# LS1C300B_176A_Msystem.net
KiCad netlist of a schematic drawn in Altium Designer
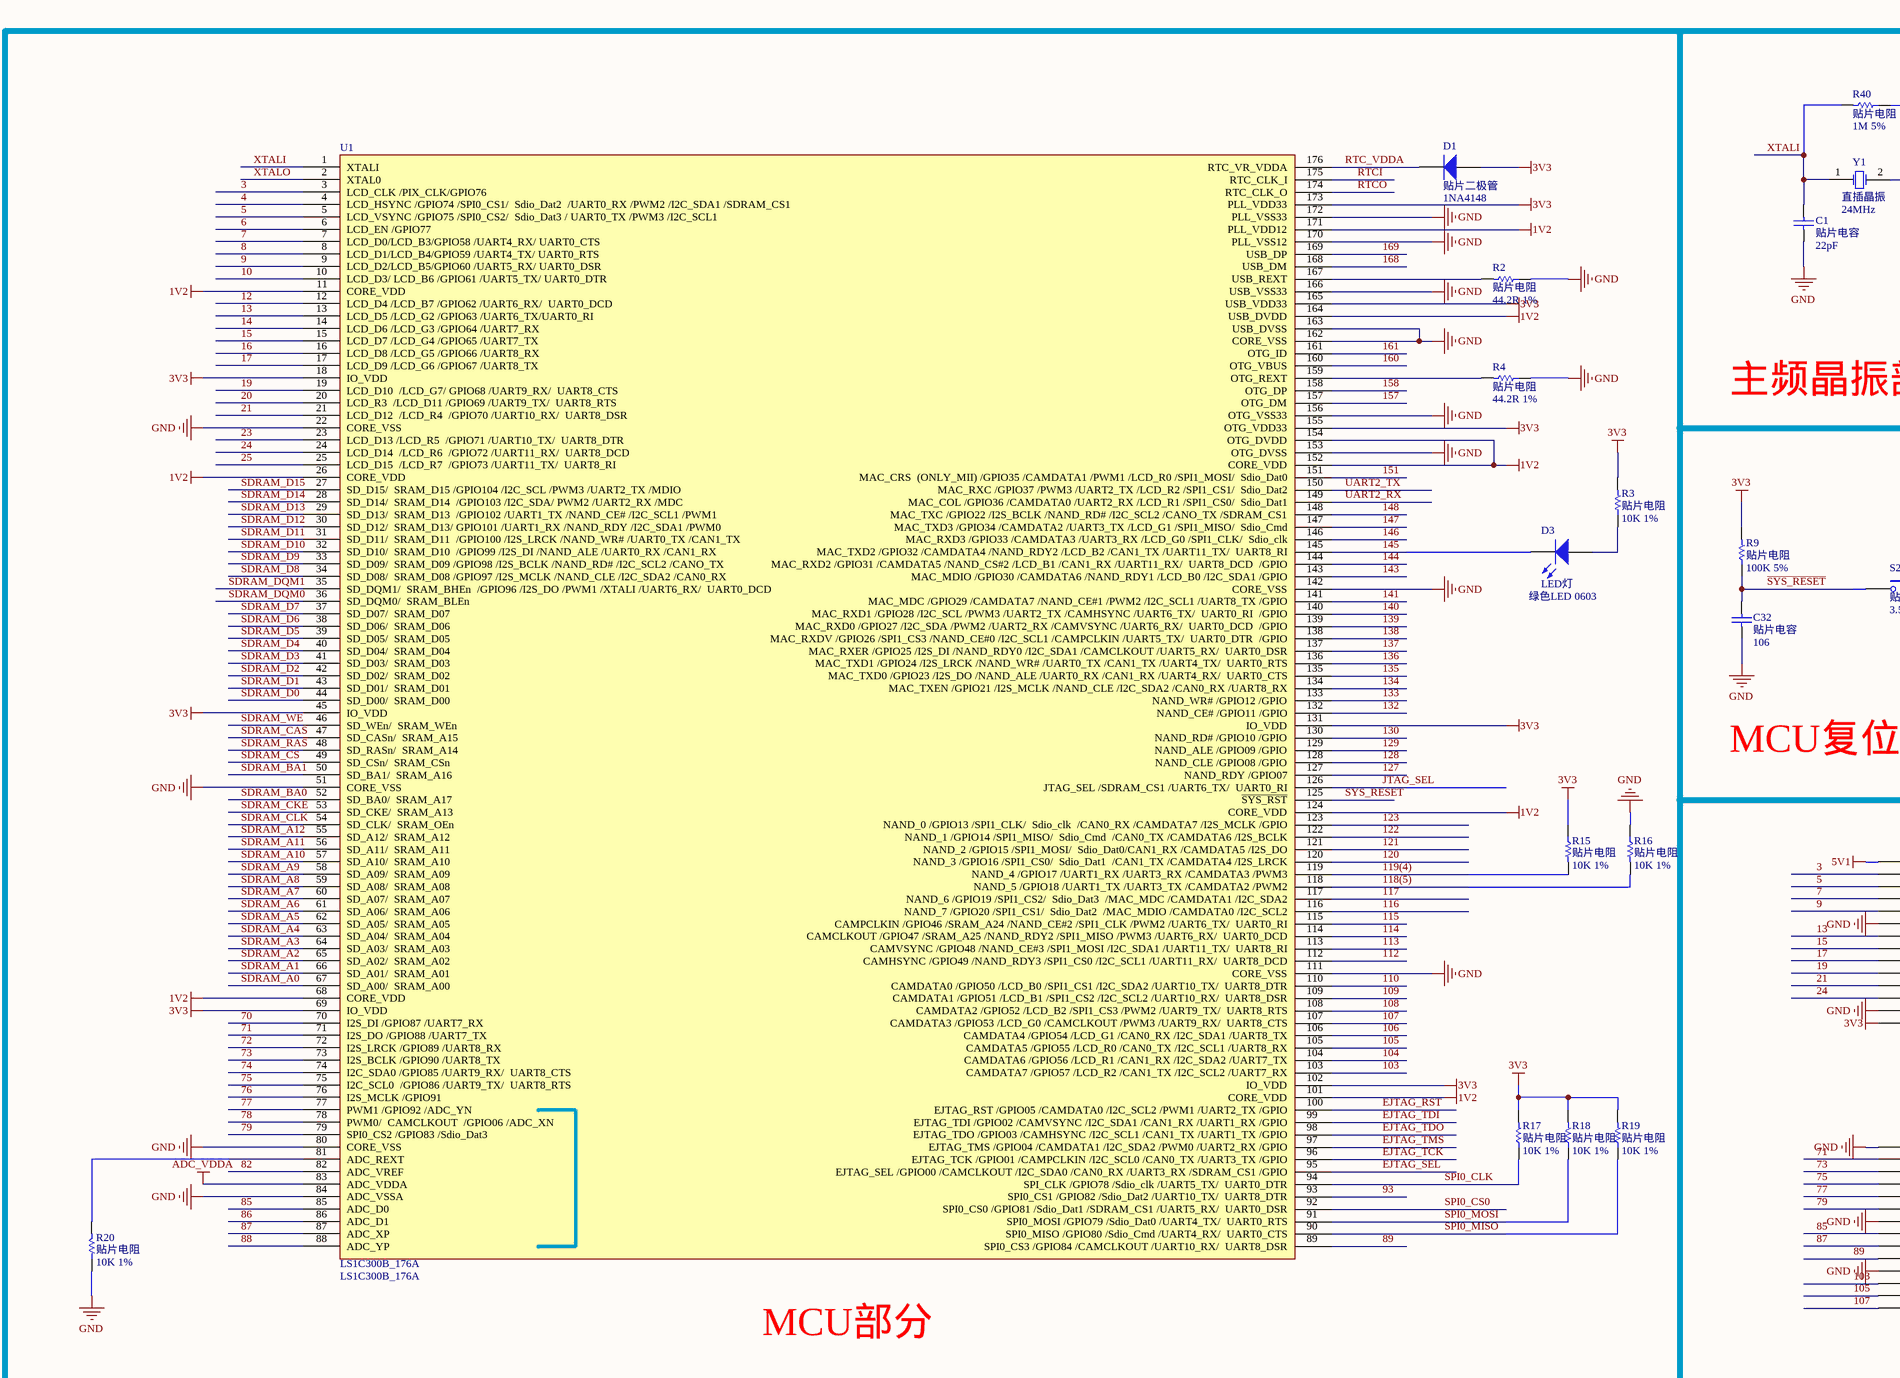
[diagram p0: LS1C300B_176A_Msystem.SchDoc, top left]
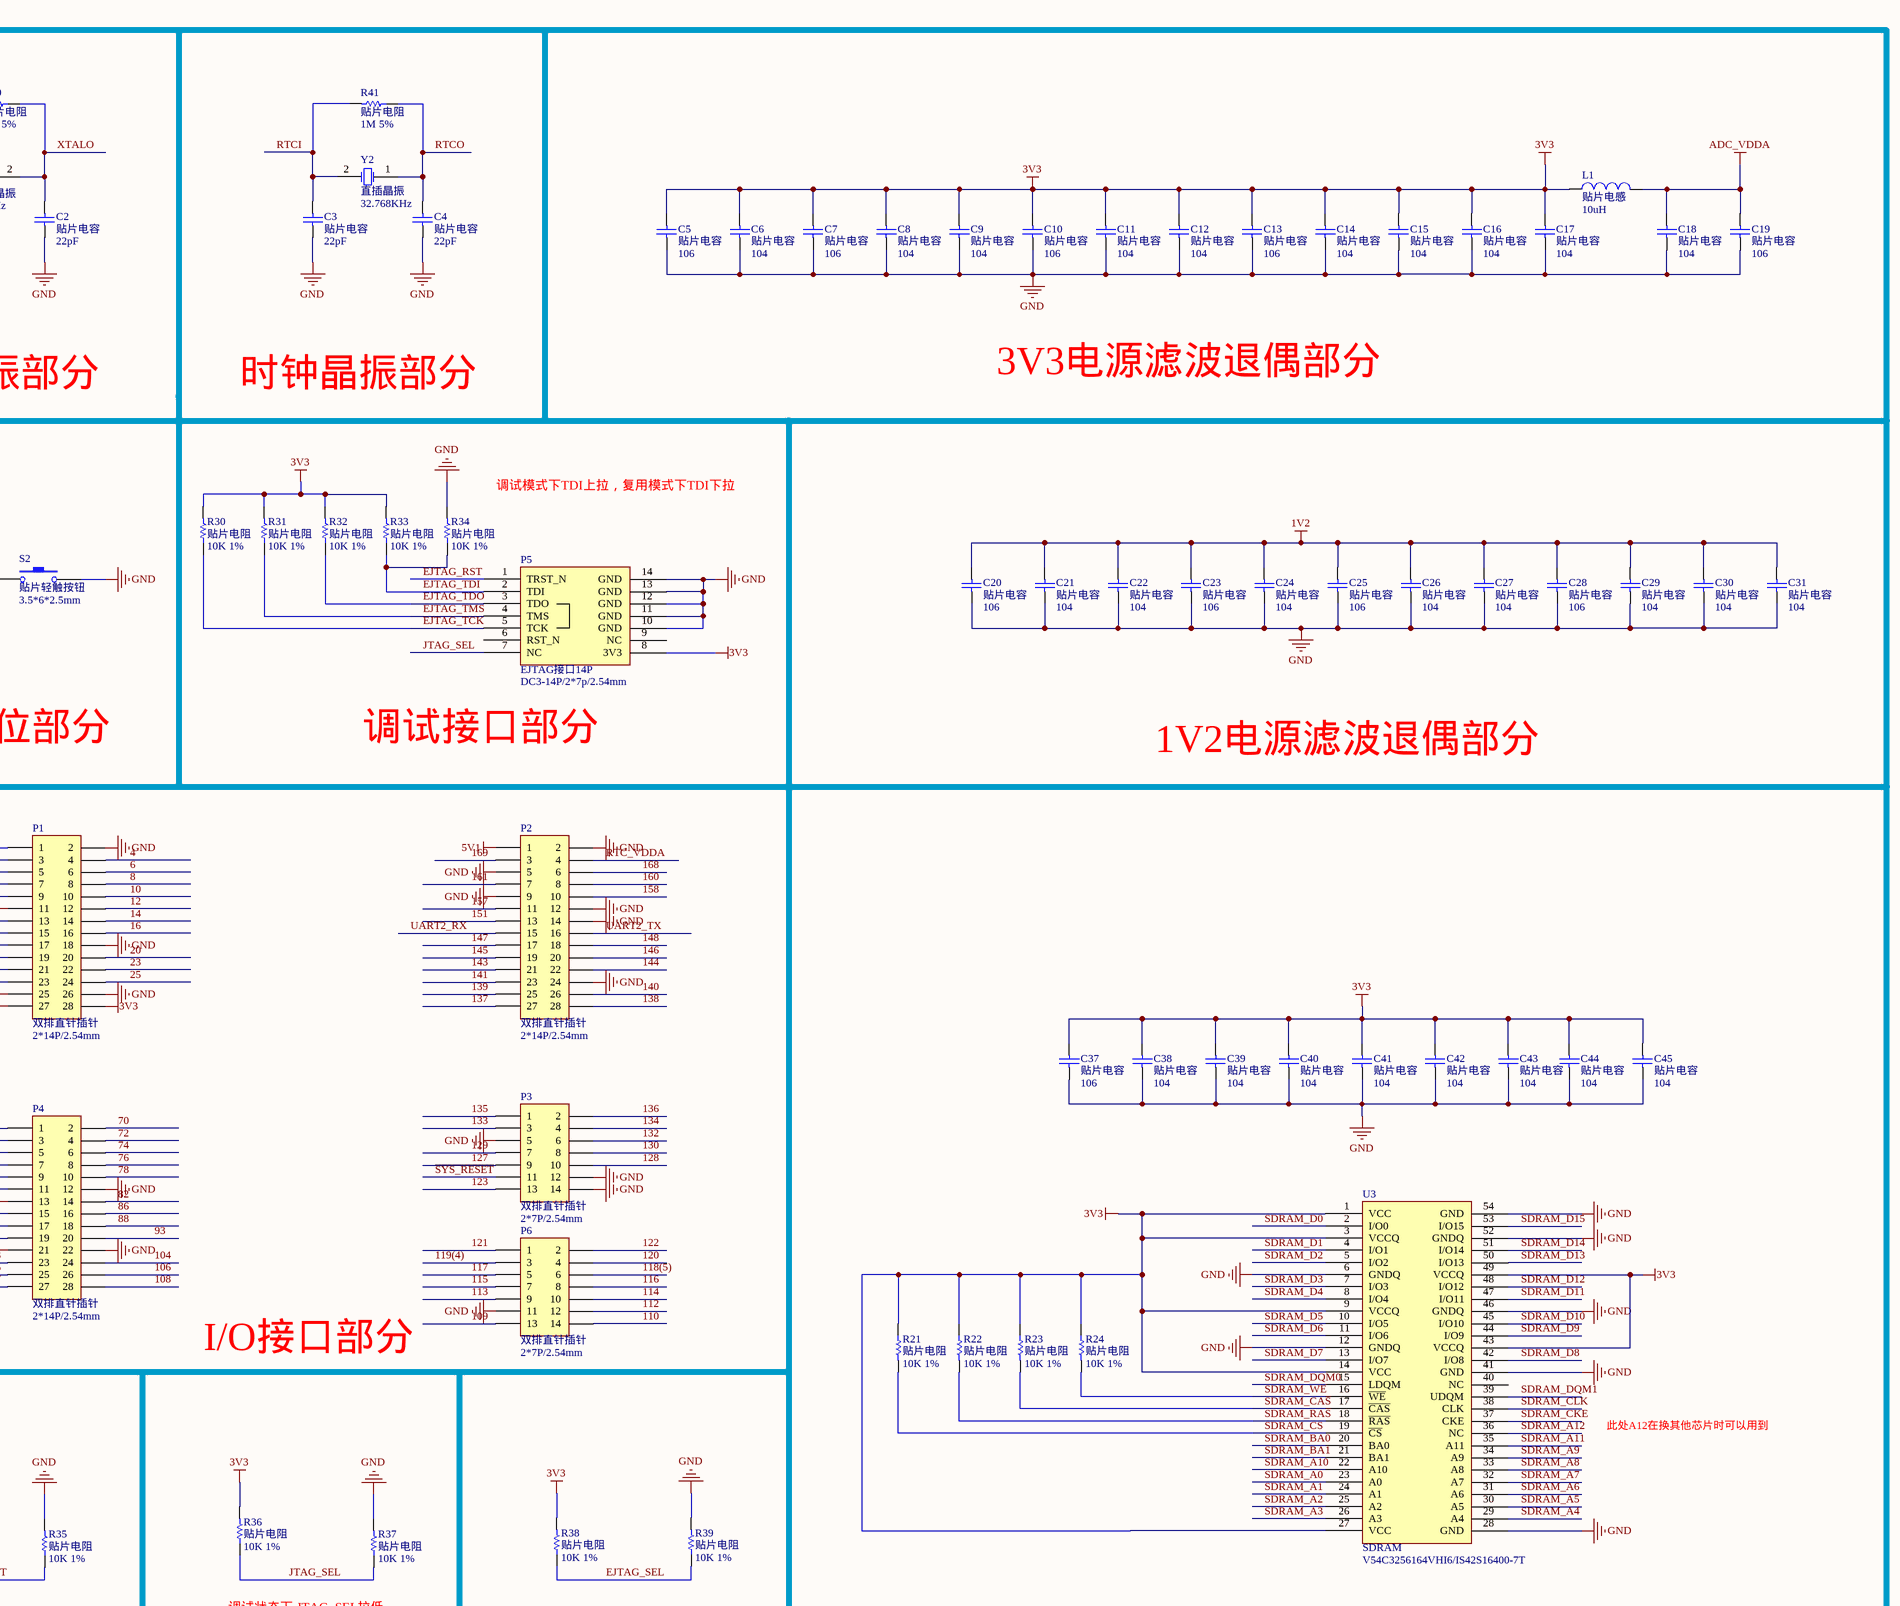
[diagram p1: LS1C300B_176A_Msystem.SchDoc, top right]
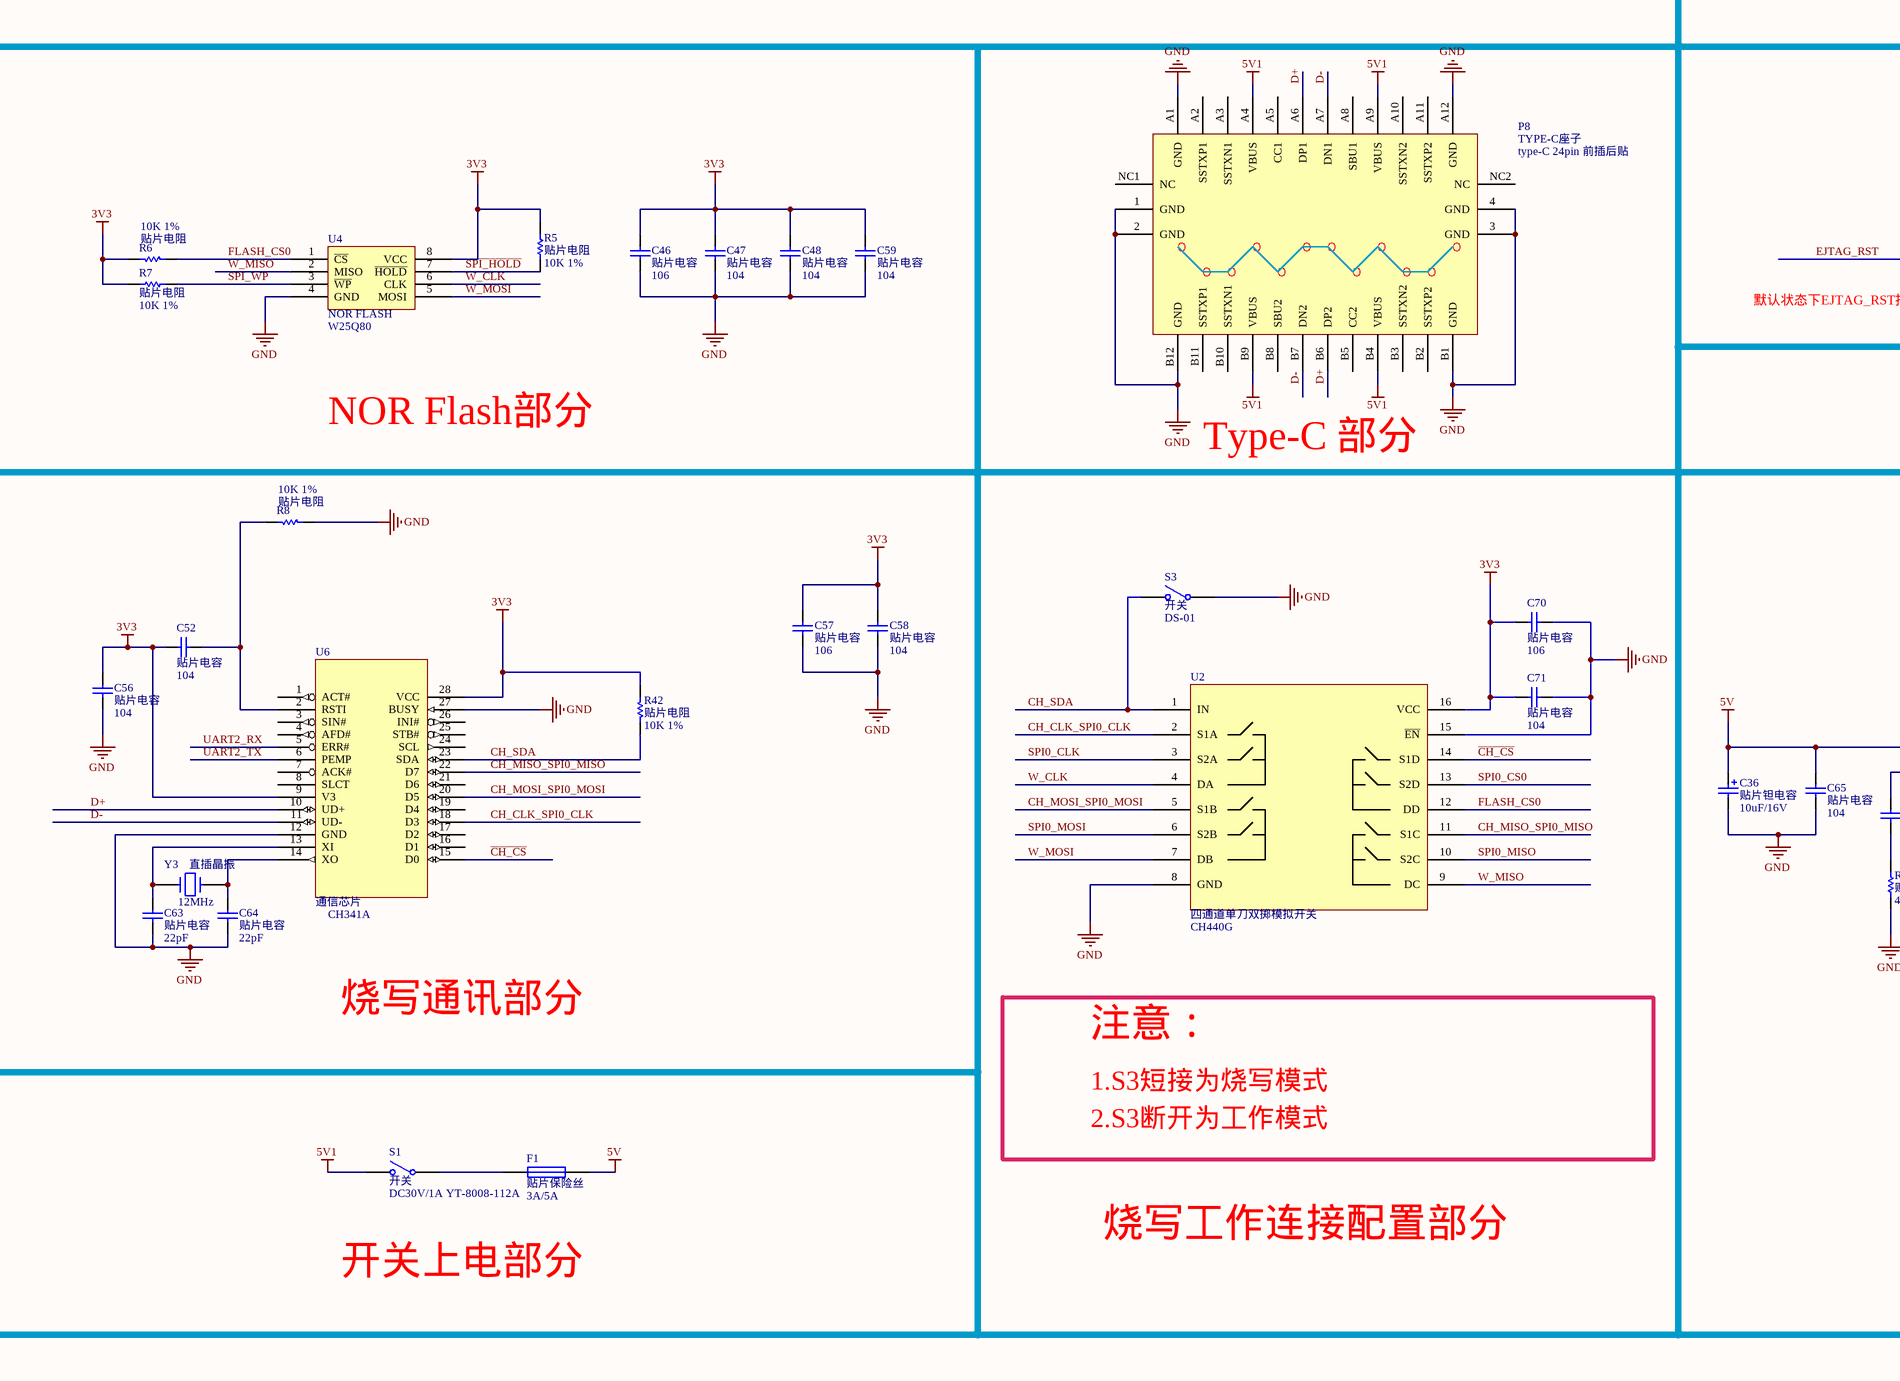
[diagram p2: LS1C300B_176A_Msystem.SchDoc, bottom left]
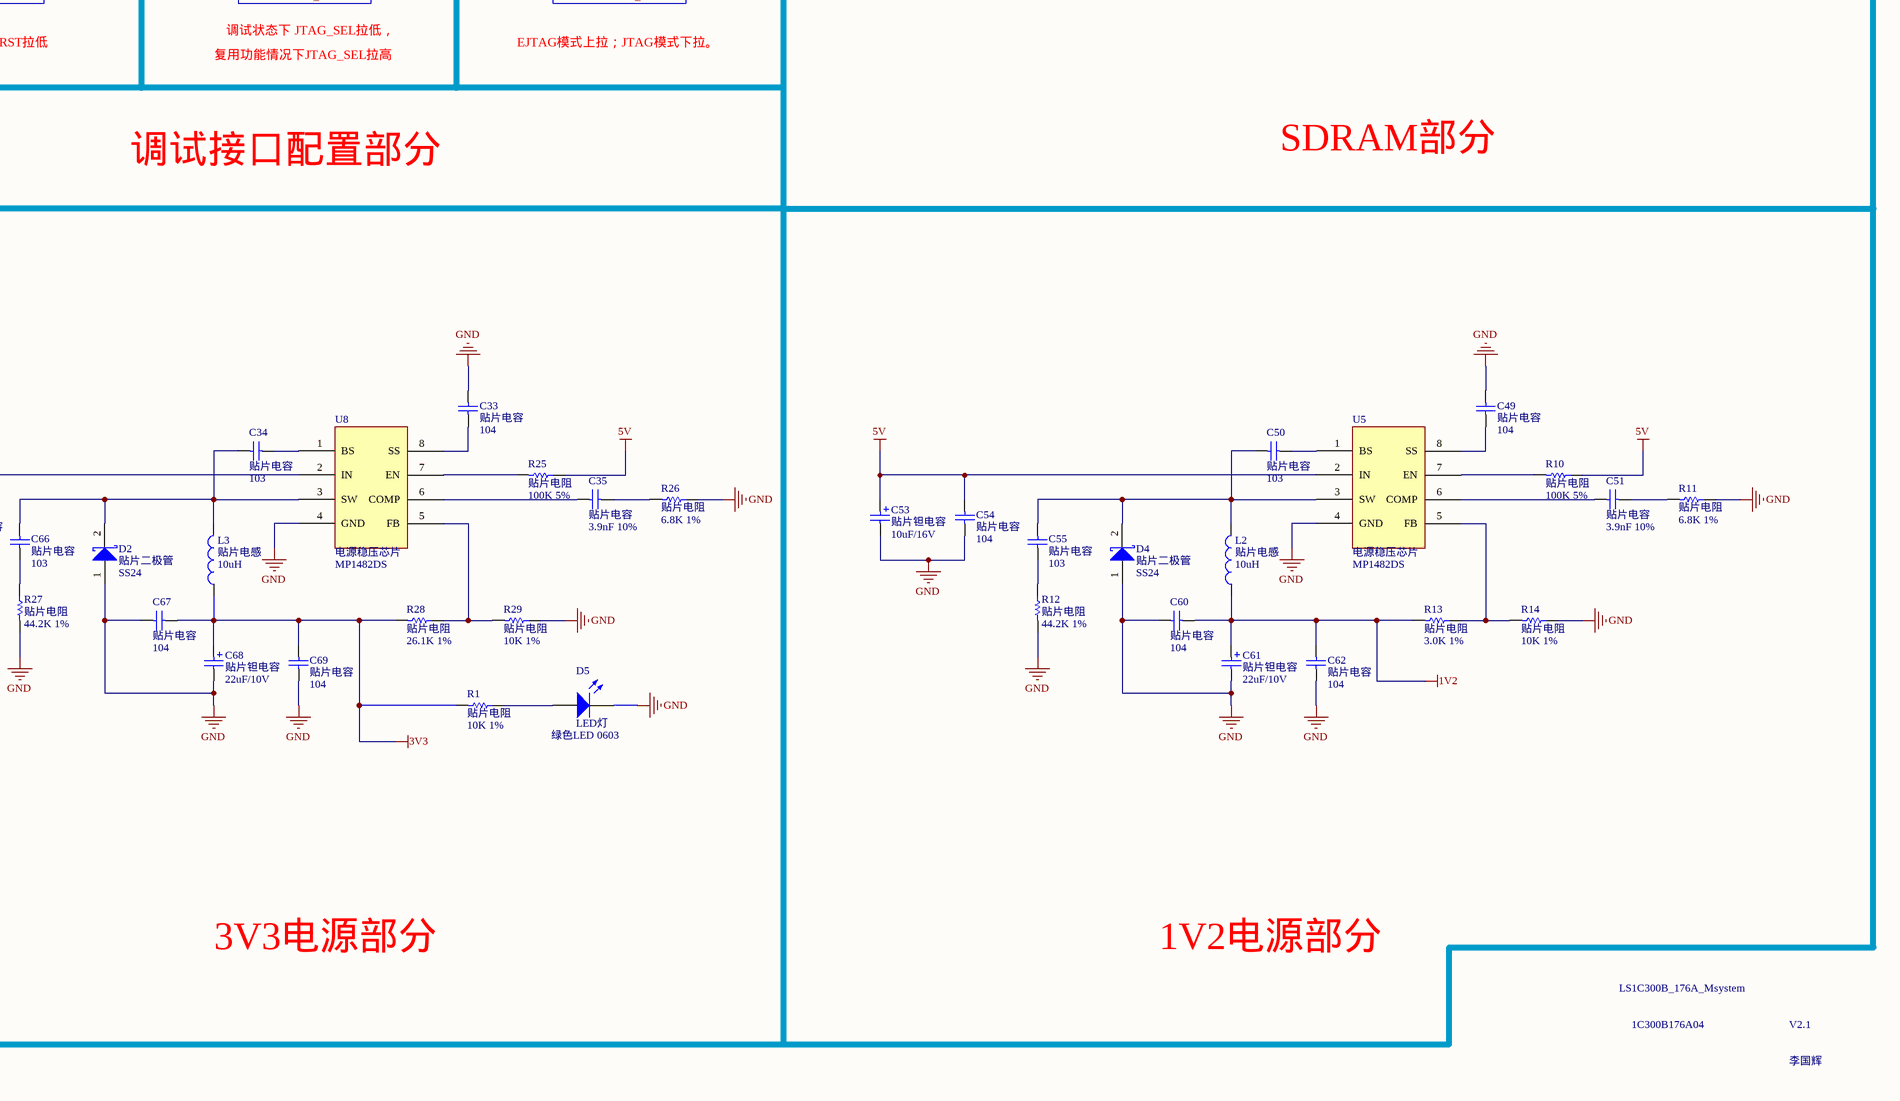
[diagram p3: LS1C300B_176A_Msystem.SchDoc, bottom right]

(export (version "E")
  (design (tool "Eeschema 10.0.6"))
  (components
    (comp (ref "C1")
      (value "贴片电容")
      (footprint "C0603")
      (description "Capacitor")
      (fields (field (name "ALTIUM_VALUE") "22pF") (field (name "PUBLISHER") "Altium Limited"))
      (libsource (lib "Miscellaneous Devices") (part "Cap"))
    )
    (comp (ref "C2")
      (value "贴片电容")
      (footprint "C0603")
      (description "Capacitor")
      (fields (field (name "ALTIUM_VALUE") "22pF") (field (name "PUBLISHER") "Altium Limited"))
      (libsource (lib "Miscellaneous Devices") (part "Cap"))
    )
    (comp (ref "C3")
      (value "贴片电容")
      (footprint "C0603")
      (description "Capacitor")
      (fields (field (name "ALTIUM_VALUE") "22pF") (field (name "PUBLISHER") "Altium Limited"))
      (libsource (lib "Miscellaneous Devices") (part "Cap"))
    )
    (comp (ref "C4")
      (value "贴片电容")
      (footprint "C0603")
      (description "Capacitor")
      (fields (field (name "ALTIUM_VALUE") "22pF") (field (name "PUBLISHER") "Altium Limited"))
      (libsource (lib "Miscellaneous Devices") (part "Cap"))
    )
    (comp (ref "C5")
      (value "贴片电容")
      (footprint "C0603")
      (description "Capacitor")
      (fields (field (name "ALTIUM_VALUE") "106") (field (name "PUBLISHER") "Altium Limited"))
      (libsource (lib "Miscellaneous Devices") (part "Cap"))
    )
    (comp (ref "C6")
      (value "贴片电容")
      (footprint "C0603")
      (description "Capacitor")
      (fields (field (name "ALTIUM_VALUE") "104") (field (name "PUBLISHER") "Altium Limited"))
      (libsource (lib "Miscellaneous Devices") (part "Cap"))
    )
    (comp (ref "C7")
      (value "贴片电容")
      (footprint "C0603")
      (description "Capacitor")
      (fields (field (name "ALTIUM_VALUE") "106") (field (name "PUBLISHER") "Altium Limited"))
      (libsource (lib "Miscellaneous Devices") (part "Cap"))
    )
    (comp (ref "C8")
      (value "贴片电容")
      (footprint "C0603")
      (description "Capacitor")
      (fields (field (name "ALTIUM_VALUE") "104") (field (name "PUBLISHER") "Altium Limited"))
      (libsource (lib "Miscellaneous Devices") (part "Cap"))
    )
    (comp (ref "C9")
      (value "贴片电容")
      (footprint "C0603")
      (description "Capacitor")
      (fields (field (name "ALTIUM_VALUE") "104") (field (name "PUBLISHER") "Altium Limited"))
      (libsource (lib "Miscellaneous Devices") (part "Cap"))
    )
    (comp (ref "C10")
      (value "贴片电容")
      (footprint "C0603")
      (description "Capacitor")
      (fields (field (name "ALTIUM_VALUE") "106") (field (name "PUBLISHER") "Altium Limited"))
      (libsource (lib "Miscellaneous Devices") (part "Cap"))
    )
    (comp (ref "C11")
      (value "贴片电容")
      (footprint "C0603")
      (description "Capacitor")
      (fields (field (name "ALTIUM_VALUE") "104") (field (name "PUBLISHER") "Altium Limited"))
      (libsource (lib "Miscellaneous Devices") (part "Cap"))
    )
    (comp (ref "C12")
      (value "贴片电容")
      (footprint "C0603")
      (description "Capacitor")
      (fields (field (name "ALTIUM_VALUE") "104") (field (name "PUBLISHER") "Altium Limited"))
      (libsource (lib "Miscellaneous Devices") (part "Cap"))
    )
    (comp (ref "C13")
      (value "贴片电容")
      (footprint "C0603")
      (description "Capacitor")
      (fields (field (name "ALTIUM_VALUE") "106") (field (name "PUBLISHER") "Altium Limited"))
      (libsource (lib "Miscellaneous Devices") (part "Cap"))
    )
    (comp (ref "C14")
      (value "贴片电容")
      (footprint "C0603")
      (description "Capacitor")
      (fields (field (name "ALTIUM_VALUE") "104") (field (name "PUBLISHER") "Altium Limited"))
      (libsource (lib "Miscellaneous Devices") (part "Cap"))
    )
    (comp (ref "C15")
      (value "贴片电容")
      (footprint "C0603")
      (description "Capacitor")
      (fields (field (name "ALTIUM_VALUE") "104") (field (name "PUBLISHER") "Altium Limited"))
      (libsource (lib "Miscellaneous Devices") (part "Cap"))
    )
    (comp (ref "C16")
      (value "贴片电容")
      (footprint "C0603")
      (description "Capacitor")
      (fields (field (name "ALTIUM_VALUE") "104") (field (name "PUBLISHER") "Altium Limited"))
      (libsource (lib "Miscellaneous Devices") (part "Cap"))
    )
    (comp (ref "C17")
      (value "贴片电容")
      (footprint "C0603")
      (description "Capacitor")
      (fields (field (name "ALTIUM_VALUE") "104") (field (name "PUBLISHER") "Altium Limited"))
      (libsource (lib "Miscellaneous Devices") (part "Cap"))
    )
    (comp (ref "C18")
      (value "贴片电容")
      (footprint "C0603")
      (description "Capacitor")
      (fields (field (name "ALTIUM_VALUE") "104") (field (name "PUBLISHER") "Altium Limited"))
      (libsource (lib "Miscellaneous Devices") (part "Cap"))
    )
    (comp (ref "C19")
      (value "贴片电容")
      (footprint "C0603")
      (description "Capacitor")
      (fields (field (name "ALTIUM_VALUE") "106") (field (name "PUBLISHER") "Altium Limited"))
      (libsource (lib "Miscellaneous Devices") (part "Cap"))
    )
    (comp (ref "C20")
      (value "贴片电容")
      (footprint "C0603")
      (description "Capacitor")
      (fields (field (name "ALTIUM_VALUE") "106") (field (name "PUBLISHER") "Altium Limited"))
      (libsource (lib "Miscellaneous Devices") (part "Cap"))
    )
    (comp (ref "C21")
      (value "贴片电容")
      (footprint "C0603")
      (description "Capacitor")
      (fields (field (name "ALTIUM_VALUE") "104") (field (name "PUBLISHER") "Altium Limited"))
      (libsource (lib "Miscellaneous Devices") (part "Cap"))
    )
    (comp (ref "C22")
      (value "贴片电容")
      (footprint "C0603")
      (description "Capacitor")
      (fields (field (name "ALTIUM_VALUE") "104") (field (name "PUBLISHER") "Altium Limited"))
      (libsource (lib "Miscellaneous Devices") (part "Cap"))
    )
    (comp (ref "C23")
      (value "贴片电容")
      (footprint "C0603")
      (description "Capacitor")
      (fields (field (name "ALTIUM_VALUE") "106") (field (name "PUBLISHER") "Altium Limited"))
      (libsource (lib "Miscellaneous Devices") (part "Cap"))
    )
    (comp (ref "C24")
      (value "贴片电容")
      (footprint "C0603")
      (description "Capacitor")
      (fields (field (name "ALTIUM_VALUE") "104") (field (name "PUBLISHER") "Altium Limited"))
      (libsource (lib "Miscellaneous Devices") (part "Cap"))
    )
    (comp (ref "C25")
      (value "贴片电容")
      (footprint "C0603")
      (description "Capacitor")
      (fields (field (name "ALTIUM_VALUE") "106") (field (name "PUBLISHER") "Altium Limited"))
      (libsource (lib "Miscellaneous Devices") (part "Cap"))
    )
    (comp (ref "C26")
      (value "贴片电容")
      (footprint "C0603")
      (description "Capacitor")
      (fields (field (name "ALTIUM_VALUE") "104") (field (name "PUBLISHER") "Altium Limited"))
      (libsource (lib "Miscellaneous Devices") (part "Cap"))
    )
    (comp (ref "C27")
      (value "贴片电容")
      (footprint "C0603")
      (description "Capacitor")
      (fields (field (name "ALTIUM_VALUE") "104") (field (name "PUBLISHER") "Altium Limited"))
      (libsource (lib "Miscellaneous Devices") (part "Cap"))
    )
    (comp (ref "C28")
      (value "贴片电容")
      (footprint "C0603")
      (description "Capacitor")
      (fields (field (name "ALTIUM_VALUE") "106") (field (name "PUBLISHER") "Altium Limited"))
      (libsource (lib "Miscellaneous Devices") (part "Cap"))
    )
    (comp (ref "C29")
      (value "贴片电容")
      (footprint "C0603")
      (description "Capacitor")
      (fields (field (name "ALTIUM_VALUE") "104") (field (name "PUBLISHER") "Altium Limited"))
      (libsource (lib "Miscellaneous Devices") (part "Cap"))
    )
    (comp (ref "C30")
      (value "贴片电容")
      (footprint "C0603")
      (description "Capacitor")
      (fields (field (name "ALTIUM_VALUE") "104") (field (name "PUBLISHER") "Altium Limited"))
      (libsource (lib "Miscellaneous Devices") (part "Cap"))
    )
    (comp (ref "C31")
      (value "贴片电容")
      (footprint "C0603")
      (description "Capacitor")
      (fields (field (name "ALTIUM_VALUE") "104") (field (name "PUBLISHER") "Altium Limited"))
      (libsource (lib "Miscellaneous Devices") (part "Cap"))
    )
    (comp (ref "C32")
      (value "贴片电容")
      (footprint "C0603")
      (description "Capacitor")
      (fields (field (name "ALTIUM_VALUE") "106") (field (name "PUBLISHER") "Altium Limited"))
      (libsource (lib "Miscellaneous Devices") (part "Cap"))
    )
    (comp (ref "C33")
      (value "贴片电容")
      (footprint "C0603")
      (description "Capacitor")
      (fields (field (name "ALTIUM_VALUE") "104") (field (name "PUBLISHER") "Altium Limited"))
      (libsource (lib "Miscellaneous Devices") (part "Cap"))
    )
    (comp (ref "C34")
      (value "贴片电容")
      (footprint "C0603")
      (description "Capacitor")
      (fields (field (name "ALTIUM_VALUE") "103") (field (name "PUBLISHER") "Altium Limited"))
      (libsource (lib "Miscellaneous Devices") (part "Cap"))
    )
    (comp (ref "C35")
      (value "贴片电容")
      (footprint "C0603")
      (description "Capacitor")
      (fields (field (name "ALTIUM_VALUE") "3.9nF 10%") (field (name "PUBLISHER") "Altium Limited"))
      (libsource (lib "Miscellaneous Devices") (part "Cap"))
    )
    (comp (ref "C36")
      (value "贴片钽电容")
      (footprint "P-C1206")
      (description "Polarized Capacitor (Axial)")
      (fields (field (name "ALTIUM_VALUE") "10uF/16V") (field (name "PUBLISHER") "Altium Limited"))
      (libsource (lib "Miscellaneous Devices") (part "Cap Pol2"))
    )
    (comp (ref "C37")
      (value "贴片电容")
      (footprint "C0603")
      (description "Capacitor")
      (fields (field (name "ALTIUM_VALUE") "106") (field (name "PUBLISHER") "Altium Limited"))
      (libsource (lib "Miscellaneous Devices") (part "Cap"))
    )
    (comp (ref "C38")
      (value "贴片电容")
      (footprint "C0603")
      (description "Capacitor")
      (fields (field (name "ALTIUM_VALUE") "104") (field (name "PUBLISHER") "Altium Limited"))
      (libsource (lib "Miscellaneous Devices") (part "Cap"))
    )
    (comp (ref "C39")
      (value "贴片电容")
      (footprint "C0603")
      (description "Capacitor")
      (fields (field (name "ALTIUM_VALUE") "104") (field (name "PUBLISHER") "Altium Limited"))
      (libsource (lib "Miscellaneous Devices") (part "Cap"))
    )
    (comp (ref "C40")
      (value "贴片电容")
      (footprint "C0603")
      (description "Capacitor")
      (fields (field (name "ALTIUM_VALUE") "104") (field (name "PUBLISHER") "Altium Limited"))
      (libsource (lib "Miscellaneous Devices") (part "Cap"))
    )
    (comp (ref "C41")
      (value "贴片电容")
      (footprint "C0603")
      (description "Capacitor")
      (fields (field (name "ALTIUM_VALUE") "104") (field (name "PUBLISHER") "Altium Limited"))
      (libsource (lib "Miscellaneous Devices") (part "Cap"))
    )
    (comp (ref "C42")
      (value "贴片电容")
      (footprint "C0603")
      (description "Capacitor")
      (fields (field (name "ALTIUM_VALUE") "104") (field (name "PUBLISHER") "Altium Limited"))
      (libsource (lib "Miscellaneous Devices") (part "Cap"))
    )
    (comp (ref "C43")
      (value "贴片电容")
      (footprint "C0603")
      (description "Capacitor")
      (fields (field (name "ALTIUM_VALUE") "104") (field (name "PUBLISHER") "Altium Limited"))
      (libsource (lib "Miscellaneous Devices") (part "Cap"))
    )
    (comp (ref "C44")
      (value "贴片电容")
      (footprint "C0603")
      (description "Capacitor")
      (fields (field (name "ALTIUM_VALUE") "104") (field (name "PUBLISHER") "Altium Limited"))
      (libsource (lib "Miscellaneous Devices") (part "Cap"))
    )
    (comp (ref "C45")
      (value "贴片电容")
      (footprint "C0603")
      (description "Capacitor")
      (fields (field (name "ALTIUM_VALUE") "104") (field (name "PUBLISHER") "Altium Limited"))
      (libsource (lib "Miscellaneous Devices") (part "Cap"))
    )
    (comp (ref "C46")
      (value "贴片电容")
      (footprint "C0603")
      (description "Capacitor")
      (fields (field (name "ALTIUM_VALUE") "106") (field (name "PUBLISHER") "Altium Limited"))
      (libsource (lib "Miscellaneous Devices") (part "Cap"))
    )
    (comp (ref "C47")
      (value "贴片电容")
      (footprint "C0603")
      (description "Capacitor")
      (fields (field (name "ALTIUM_VALUE") "104") (field (name "PUBLISHER") "Altium Limited"))
      (libsource (lib "Miscellaneous Devices") (part "Cap"))
    )
    (comp (ref "C48")
      (value "贴片电容")
      (footprint "C0603")
      (description "Capacitor")
      (fields (field (name "ALTIUM_VALUE") "104") (field (name "PUBLISHER") "Altium Limited"))
      (libsource (lib "Miscellaneous Devices") (part "Cap"))
    )
    (comp (ref "C49")
      (value "贴片电容")
      (footprint "C0603")
      (description "Capacitor")
      (fields (field (name "ALTIUM_VALUE") "104") (field (name "PUBLISHER") "Altium Limited"))
      (libsource (lib "Miscellaneous Devices") (part "Cap"))
    )
    (comp (ref "C50")
      (value "贴片电容")
      (footprint "C0603")
      (description "Capacitor")
      (fields (field (name "ALTIUM_VALUE") "103") (field (name "PUBLISHER") "Altium Limited"))
      (libsource (lib "Miscellaneous Devices") (part "Cap"))
    )
    (comp (ref "C51")
      (value "贴片电容")
      (footprint "C0603")
      (description "Capacitor")
      (fields (field (name "ALTIUM_VALUE") "3.9nF 10%") (field (name "PUBLISHER") "Altium Limited"))
      (libsource (lib "Miscellaneous Devices") (part "Cap"))
    )
    (comp (ref "C52")
      (value "贴片电容")
      (footprint "C0603")
      (description "Capacitor")
      (fields (field (name "ALTIUM_VALUE") "104") (field (name "PUBLISHER") "Altium Limited"))
      (libsource (lib "Miscellaneous Devices") (part "Cap"))
    )
    (comp (ref "C53")
      (value "贴片钽电容")
      (footprint "P-C1206")
      (description "Polarized Capacitor (Axial)")
      (fields (field (name "ALTIUM_VALUE") "10uF/16V") (field (name "PUBLISHER") "Altium Limited"))
      (libsource (lib "Miscellaneous Devices") (part "Cap Pol2"))
    )
    (comp (ref "C54")
      (value "贴片电容")
      (footprint "C0603")
      (description "Capacitor")
      (fields (field (name "ALTIUM_VALUE") "104") (field (name "PUBLISHER") "Altium Limited"))
      (libsource (lib "Miscellaneous Devices") (part "Cap"))
    )
    (comp (ref "C55")
      (value "贴片电容")
      (footprint "C0603")
      (description "Capacitor")
      (fields (field (name "ALTIUM_VALUE") "103") (field (name "PUBLISHER") "Altium Limited"))
      (libsource (lib "Miscellaneous Devices") (part "Cap"))
    )
    (comp (ref "C56")
      (value "贴片电容")
      (footprint "C0603")
      (description "Capacitor")
      (fields (field (name "ALTIUM_VALUE") "104") (field (name "PUBLISHER") "Altium Limited"))
      (libsource (lib "Miscellaneous Devices") (part "Cap"))
    )
    (comp (ref "C57")
      (value "贴片电容")
      (footprint "C0603")
      (description "Capacitor")
      (fields (field (name "ALTIUM_VALUE") "106") (field (name "PUBLISHER") "Altium Limited"))
      (libsource (lib "Miscellaneous Devices") (part "Cap"))
    )
    (comp (ref "C58")
      (value "贴片电容")
      (footprint "C0603")
      (description "Capacitor")
      (fields (field (name "ALTIUM_VALUE") "104") (field (name "PUBLISHER") "Altium Limited"))
      (libsource (lib "Miscellaneous Devices") (part "Cap"))
    )
    (comp (ref "C59")
      (value "贴片电容")
      (footprint "C0603")
      (description "Capacitor")
      (fields (field (name "ALTIUM_VALUE") "104") (field (name "PUBLISHER") "Altium Limited"))
      (libsource (lib "Miscellaneous Devices") (part "Cap"))
    )
    (comp (ref "C60")
      (value "贴片电容")
      (footprint "C0603")
      (description "Capacitor")
      (fields (field (name "ALTIUM_VALUE") "104") (field (name "PUBLISHER") "Altium Limited"))
      (libsource (lib "Miscellaneous Devices") (part "Cap"))
    )
    (comp (ref "C61")
      (value "贴片钽电容")
      (footprint "P-C1206")
      (description "Polarized Capacitor (Axial)")
      (fields (field (name "ALTIUM_VALUE") "22uF/10V") (field (name "PUBLISHER") "Altium Limited"))
      (libsource (lib "Miscellaneous Devices") (part "Cap Pol2"))
    )
    (comp (ref "C62")
      (value "贴片电容")
      (footprint "C0603")
      (description "Capacitor")
      (fields (field (name "ALTIUM_VALUE") "104") (field (name "PUBLISHER") "Altium Limited"))
      (libsource (lib "Miscellaneous Devices") (part "Cap"))
    )
    (comp (ref "C63")
      (value "贴片电容")
      (footprint "C0603")
      (description "Capacitor")
      (fields (field (name "ALTIUM_VALUE") "22pF") (field (name "PUBLISHER") "Altium Limited"))
      (libsource (lib "Miscellaneous Devices") (part "Cap"))
    )
    (comp (ref "C64")
      (value "贴片电容")
      (footprint "C0603")
      (description "Capacitor")
      (fields (field (name "ALTIUM_VALUE") "22pF") (field (name "PUBLISHER") "Altium Limited"))
      (libsource (lib "Miscellaneous Devices") (part "Cap"))
    )
    (comp (ref "C65")
      (value "贴片电容")
      (footprint "C0603")
      (description "Capacitor")
      (fields (field (name "ALTIUM_VALUE") "104") (field (name "PUBLISHER") "Altium Limited"))
      (libsource (lib "Miscellaneous Devices") (part "Cap"))
    )
    (comp (ref "C66")
      (value "贴片电容")
      (footprint "C0603")
      (description "Capacitor")
      (fields (field (name "ALTIUM_VALUE") "103") (field (name "PUBLISHER") "Altium Limited"))
      (libsource (lib "Miscellaneous Devices") (part "Cap"))
    )
    (comp (ref "C67")
      (value "贴片电容")
      (footprint "C0603")
      (description "Capacitor")
      (fields (field (name "ALTIUM_VALUE") "104") (field (name "PUBLISHER") "Altium Limited"))
      (libsource (lib "Miscellaneous Devices") (part "Cap"))
    )
    (comp (ref "C68")
      (value "贴片钽电容")
      (footprint "P-C1206")
      (description "Polarized Capacitor (Axial)")
      (fields (field (name "ALTIUM_VALUE") "22uF/10V") (field (name "PUBLISHER") "Altium Limited"))
      (libsource (lib "Miscellaneous Devices") (part "Cap Pol2"))
    )
    (comp (ref "C69")
      (value "贴片电容")
      (footprint "C0603")
      (description "Capacitor")
      (fields (field (name "ALTIUM_VALUE") "104") (field (name "PUBLISHER") "Altium Limited"))
      (libsource (lib "Miscellaneous Devices") (part "Cap"))
    )
    (comp (ref "C70")
      (value "贴片电容")
      (footprint "C0603")
      (description "Capacitor")
      (fields (field (name "ALTIUM_VALUE") "106") (field (name "PUBLISHER") "Altium Limited"))
      (libsource (lib "Miscellaneous Devices") (part "Cap"))
    )
    (comp (ref "C71")
      (value "贴片电容")
      (footprint "C0603")
      (description "Capacitor")
      (fields (field (name "ALTIUM_VALUE") "104") (field (name "PUBLISHER") "Altium Limited"))
      (libsource (lib "Miscellaneous Devices") (part "Cap"))
    )
    (comp (ref "D1")
      (value "贴片二极管")
      (footprint "LL-34")
      (description "Default Diode")
      (fields (field (name "ALTIUM_VALUE") "1NA4148") (field (name "PUBLISHER") "Altium Limited"))
      (libsource (lib "Miscellaneous Devices") (part "Diode"))
    )
    (comp (ref "D2")
      (value "贴片二极管")
      (footprint "DO-214AC")
      (fields (field (name "ALTIUM_VALUE") "SS24"))
      (libsource (lib "LGHLIB") (part "1N47xx"))
    )
    (comp (ref "D3")
      (value "LED灯")
      (footprint "LED-0603")
      (description "Typical INFRARED GaAs LED")
      (fields (field (name "ALTIUM_VALUE") "绿色LED 0603") (field (name "PUBLISHER") "Altium Limited"))
      (libsource (lib "Miscellaneous Devices") (part "LED0"))
    )
    (comp (ref "D4")
      (value "贴片二极管")
      (footprint "DO-214AC")
      (fields (field (name "ALTIUM_VALUE") "SS24"))
      (libsource (lib "LGHLIB") (part "1N47xx"))
    )
    (comp (ref "D5")
      (value "LED灯")
      (footprint "LED-0603")
      (description "Typical INFRARED GaAs LED")
      (fields (field (name "ALTIUM_VALUE") "绿色LED 0603") (field (name "PUBLISHER") "Altium Limited"))
      (libsource (lib "Miscellaneous Devices") (part "LED0"))
    )
    (comp (ref "F1")
      (value "贴片保险丝")
      (footprint "R1206")
      (description "Fuse")
      (fields (field (name "ALTIUM_VALUE") "3A/5A") (field (name "PUBLISHER") "Altium Limited"))
      (libsource (lib "Miscellaneous Devices") (part "Fuse 1"))
    )
    (comp (ref "L1")
      (value "贴片电感")
      (footprint "L0603")
      (description "Inductor")
      (fields (field (name "ALTIUM_VALUE") "10uH") (field (name "PUBLISHER") "Altium Limited"))
      (libsource (lib "Miscellaneous Devices") (part "Inductor"))
    )
    (comp (ref "L2")
      (value "贴片电感")
      (footprint "CD75")
      (description "Inductor")
      (fields (field (name "ALTIUM_VALUE") "10uH") (field (name "PUBLISHER") "Altium Limited"))
      (libsource (lib "Miscellaneous Devices") (part "Inductor"))
    )
    (comp (ref "L3")
      (value "贴片电感")
      (footprint "CD75")
      (description "Inductor")
      (fields (field (name "ALTIUM_VALUE") "10uH") (field (name "PUBLISHER") "Altium Limited"))
      (libsource (lib "Miscellaneous Devices") (part "Inductor"))
    )
    (comp (ref "P1")
      (value "双排直针插针")
      (footprint "HDR2X14")
      (description "Header, 14-Pin, Dual row")
      (fields (field (name "ALTIUM_VALUE") "2*14P/2.54mm") (field (name "PUBLISHER") "Altium Limited"))
      (libsource (lib "Miscellaneous Connectors") (part "MHDR2X14"))
    )
    (comp (ref "P2")
      (value "双排直针插针")
      (footprint "HDR2X14")
      (description "Header, 14-Pin, Dual row")
      (fields (field (name "ALTIUM_VALUE") "2*14P/2.54mm") (field (name "PUBLISHER") "Altium Limited"))
      (libsource (lib "Miscellaneous Connectors") (part "MHDR2X14"))
    )
    (comp (ref "P3")
      (value "双排直针插针")
      (footprint "HDR2X7")
      (description "Header, 7-Pin, Dual row")
      (fields (field (name "ALTIUM_VALUE") "2*7P/2.54mm") (field (name "PUBLISHER") "Altium Limited"))
      (libsource (lib "Miscellaneous Connectors") (part "MHDR2X7"))
    )
    (comp (ref "P4")
      (value "双排直针插针")
      (footprint "HDR2X14")
      (description "Header, 14-Pin, Dual row")
      (fields (field (name "ALTIUM_VALUE") "2*14P/2.54mm") (field (name "PUBLISHER") "Altium Limited"))
      (libsource (lib "Miscellaneous Connectors") (part "MHDR2X14"))
    )
    (comp (ref "P5")
      (value "EJTAG接口14P")
      (footprint "DC3-14P")
      (fields (field (name "ALTIUM_VALUE") "DC3-14P/2*7p/2.54mm"))
      (libsource (lib "LGHLIB") (part "EJTAG-14P"))
    )
    (comp (ref "P6")
      (value "双排直针插针")
      (footprint "HDR2X7")
      (description "Header, 7-Pin, Dual row")
      (fields (field (name "ALTIUM_VALUE") "2*7P/2.54mm") (field (name "PUBLISHER") "Altium Limited"))
      (libsource (lib "Miscellaneous Connectors") (part "MHDR2X7"))
    )
    (comp (ref "P8")
      (value "TYPE-C座子")
      (footprint "Type-C-24pin")
      (description "TYPE-C座子，24pin ，可用于大电流，四脚插板，前插后贴")
      (fields (field (name "ALTIUM_VALUE") "type-C 24pin 前插后贴"))
      (libsource (lib "LGHLIB") (part "Type-C-24PIN"))
    )
    (comp (ref "R1")
      (value "贴片电阻")
      (footprint "R0603")
      (description "Resistor")
      (fields (field (name "ALTIUM_VALUE") "10K 1%") (field (name "PUBLISHER") "Altium Limited"))
      (libsource (lib "Miscellaneous Devices") (part "Res1"))
    )
    (comp (ref "R2")
      (value "贴片电阻")
      (footprint "R0603")
      (description "Resistor")
      (fields (field (name "ALTIUM_VALUE") "44.2R 1%") (field (name "PUBLISHER") "Altium Limited"))
      (libsource (lib "Miscellaneous Devices") (part "Res1"))
    )
    (comp (ref "R3")
      (value "贴片电阻")
      (footprint "R0603")
      (description "Resistor")
      (fields (field (name "ALTIUM_VALUE") "10K 1%") (field (name "PUBLISHER") "Altium Limited"))
      (libsource (lib "Miscellaneous Devices") (part "Res1"))
    )
    (comp (ref "R4")
      (value "贴片电阻")
      (footprint "R0603")
      (description "Resistor")
      (fields (field (name "ALTIUM_VALUE") "44.2R 1%") (field (name "PUBLISHER") "Altium Limited"))
      (libsource (lib "Miscellaneous Devices") (part "Res1"))
    )
    (comp (ref "R5")
      (value "贴片电阻")
      (footprint "R0603")
      (description "Resistor")
      (fields (field (name "ALTIUM_VALUE") "10K 1%") (field (name "PUBLISHER") "Altium Limited"))
      (libsource (lib "Miscellaneous Devices") (part "Res1"))
    )
    (comp (ref "R6")
      (value "贴片电阻")
      (footprint "R0603")
      (description "Resistor")
      (fields (field (name "ALTIUM_VALUE") "10K 1%") (field (name "PUBLISHER") "Altium Limited"))
      (libsource (lib "Miscellaneous Devices") (part "Res1"))
    )
    (comp (ref "R7")
      (value "贴片电阻")
      (footprint "R0603")
      (description "Resistor")
      (fields (field (name "ALTIUM_VALUE") "10K 1%") (field (name "PUBLISHER") "Altium Limited"))
      (libsource (lib "Miscellaneous Devices") (part "Res1"))
    )
    (comp (ref "R8")
      (value "贴片电阻")
      (footprint "R0603")
      (description "Resistor")
      (fields (field (name "ALTIUM_VALUE") "10K 1%") (field (name "PUBLISHER") "Altium Limited"))
      (libsource (lib "Miscellaneous Devices") (part "Res1"))
    )
    (comp (ref "R9")
      (value "贴片电阻")
      (footprint "R0603")
      (description "Resistor")
      (fields (field (name "ALTIUM_VALUE") "100K 5%") (field (name "PUBLISHER") "Altium Limited"))
      (libsource (lib "Miscellaneous Devices") (part "Res1"))
    )
    (comp (ref "R10")
      (value "贴片电阻")
      (footprint "R0603")
      (description "Resistor")
      (fields (field (name "ALTIUM_VALUE") "100K 5%") (field (name "PUBLISHER") "Altium Limited"))
      (libsource (lib "Miscellaneous Devices") (part "Res1"))
    )
    (comp (ref "R11")
      (value "贴片电阻")
      (footprint "R0603")
      (description "Resistor")
      (fields (field (name "ALTIUM_VALUE") "6.8K 1%") (field (name "PUBLISHER") "Altium Limited"))
      (libsource (lib "Miscellaneous Devices") (part "Res1"))
    )
    (comp (ref "R12")
      (value "贴片电阻")
      (footprint "R0603")
      (description "Resistor")
      (fields (field (name "ALTIUM_VALUE") "44.2K 1%") (field (name "PUBLISHER") "Altium Limited"))
      (libsource (lib "Miscellaneous Devices") (part "Res1"))
    )
    (comp (ref "R13")
      (value "贴片电阻")
      (footprint "R0603")
      (description "Resistor")
      (fields (field (name "ALTIUM_VALUE") "3.0K 1%") (field (name "PUBLISHER") "Altium Limited"))
      (libsource (lib "Miscellaneous Devices") (part "Res1"))
    )
    (comp (ref "R14")
      (value "贴片电阻")
      (footprint "R0603")
      (description "Resistor")
      (fields (field (name "ALTIUM_VALUE") "10K 1%") (field (name "PUBLISHER") "Altium Limited"))
      (libsource (lib "Miscellaneous Devices") (part "Res1"))
    )
    (comp (ref "R15")
      (value "贴片电阻")
      (footprint "R0603")
      (description "Resistor")
      (fields (field (name "ALTIUM_VALUE") "10K 1%") (field (name "PUBLISHER") "Altium Limited"))
      (libsource (lib "Miscellaneous Devices") (part "Res1"))
    )
    (comp (ref "R16")
      (value "贴片电阻")
      (footprint "R0603")
      (description "Resistor")
      (fields (field (name "ALTIUM_VALUE") "10K 1%") (field (name "PUBLISHER") "Altium Limited"))
      (libsource (lib "Miscellaneous Devices") (part "Res1"))
    )
    (comp (ref "R17")
      (value "贴片电阻")
      (footprint "R0603")
      (description "Resistor")
      (fields (field (name "ALTIUM_VALUE") "10K 1%") (field (name "PUBLISHER") "Altium Limited"))
      (libsource (lib "Miscellaneous Devices") (part "Res1"))
    )
    (comp (ref "R18")
      (value "贴片电阻")
      (footprint "R0603")
      (description "Resistor")
      (fields (field (name "ALTIUM_VALUE") "10K 1%") (field (name "PUBLISHER") "Altium Limited"))
      (libsource (lib "Miscellaneous Devices") (part "Res1"))
    )
    (comp (ref "R19")
      (value "贴片电阻")
      (footprint "R0603")
      (description "Resistor")
      (fields (field (name "ALTIUM_VALUE") "10K 1%") (field (name "PUBLISHER") "Altium Limited"))
      (libsource (lib "Miscellaneous Devices") (part "Res1"))
    )
    (comp (ref "R20")
      (value "贴片电阻")
      (footprint "R0603")
      (description "Resistor")
      (fields (field (name "ALTIUM_VALUE") "10K 1%") (field (name "PUBLISHER") "Altium Limited"))
      (libsource (lib "Miscellaneous Devices") (part "Res1"))
    )
    (comp (ref "R21")
      (value "贴片电阻")
      (footprint "R0603")
      (description "Resistor")
      (fields (field (name "ALTIUM_VALUE") "10K 1%") (field (name "PUBLISHER") "Altium Limited"))
      (libsource (lib "Miscellaneous Devices") (part "Res1"))
    )
    (comp (ref "R22")
      (value "贴片电阻")
      (footprint "R0603")
      (description "Resistor")
      (fields (field (name "ALTIUM_VALUE") "10K 1%") (field (name "PUBLISHER") "Altium Limited"))
      (libsource (lib "Miscellaneous Devices") (part "Res1"))
    )
    (comp (ref "R23")
      (value "贴片电阻")
      (footprint "R0603")
      (description "Resistor")
      (fields (field (name "ALTIUM_VALUE") "10K 1%") (field (name "PUBLISHER") "Altium Limited"))
      (libsource (lib "Miscellaneous Devices") (part "Res1"))
    )
    (comp (ref "R24")
      (value "贴片电阻")
      (footprint "R0603")
      (description "Resistor")
      (fields (field (name "ALTIUM_VALUE") "10K 1%") (field (name "PUBLISHER") "Altium Limited"))
      (libsource (lib "Miscellaneous Devices") (part "Res1"))
    )
    (comp (ref "R25")
      (value "贴片电阻")
      (footprint "R0603")
      (description "Resistor")
      (fields (field (name "ALTIUM_VALUE") "100K 5%") (field (name "PUBLISHER") "Altium Limited"))
      (libsource (lib "Miscellaneous Devices") (part "Res1"))
    )
    (comp (ref "R26")
      (value "贴片电阻")
      (footprint "R0603")
      (description "Resistor")
      (fields (field (name "ALTIUM_VALUE") "6.8K 1%") (field (name "PUBLISHER") "Altium Limited"))
      (libsource (lib "Miscellaneous Devices") (part "Res1"))
    )
    (comp (ref "R27")
      (value "贴片电阻")
      (footprint "R0603")
      (description "Resistor")
      (fields (field (name "ALTIUM_VALUE") "44.2K 1%") (field (name "PUBLISHER") "Altium Limited"))
      (libsource (lib "Miscellaneous Devices") (part "Res1"))
    )
    (comp (ref "R28")
      (value "贴片电阻")
      (footprint "R0603")
      (description "Resistor")
      (fields (field (name "ALTIUM_VALUE") "26.1K 1%") (field (name "PUBLISHER") "Altium Limited"))
      (libsource (lib "Miscellaneous Devices") (part "Res1"))
    )
    (comp (ref "R29")
      (value "贴片电阻")
      (footprint "R0603")
      (description "Resistor")
      (fields (field (name "ALTIUM_VALUE") "10K 1%") (field (name "PUBLISHER") "Altium Limited"))
      (libsource (lib "Miscellaneous Devices") (part "Res1"))
    )
    (comp (ref "R30")
      (value "贴片电阻")
      (footprint "R0603")
      (description "Resistor")
      (fields (field (name "ALTIUM_VALUE") "10K 1%") (field (name "PUBLISHER") "Altium Limited"))
      (libsource (lib "Miscellaneous Devices") (part "Res1"))
    )
    (comp (ref "R31")
      (value "贴片电阻")
      (footprint "R0603")
      (description "Resistor")
      (fields (field (name "ALTIUM_VALUE") "10K 1%") (field (name "PUBLISHER") "Altium Limited"))
      (libsource (lib "Miscellaneous Devices") (part "Res1"))
    )
    (comp (ref "R32")
      (value "贴片电阻")
      (footprint "R0603")
      (description "Resistor")
      (fields (field (name "ALTIUM_VALUE") "10K 1%") (field (name "PUBLISHER") "Altium Limited"))
      (libsource (lib "Miscellaneous Devices") (part "Res1"))
    )
    (comp (ref "R33")
      (value "贴片电阻")
      (footprint "R0603")
      (description "Resistor")
      (fields (field (name "ALTIUM_VALUE") "10K 1%") (field (name "PUBLISHER") "Altium Limited"))
      (libsource (lib "Miscellaneous Devices") (part "Res1"))
    )
    (comp (ref "R34")
      (value "贴片电阻")
      (footprint "R0603")
      (description "Resistor")
      (fields (field (name "ALTIUM_VALUE") "10K 1%") (field (name "PUBLISHER") "Altium Limited"))
      (libsource (lib "Miscellaneous Devices") (part "Res1"))
    )
    (comp (ref "R35")
      (value "贴片电阻")
      (footprint "R0603")
      (description "Resistor")
      (fields (field (name "ALTIUM_VALUE") "10K 1%") (field (name "PUBLISHER") "Altium Limited"))
      (libsource (lib "Miscellaneous Devices") (part "Res1"))
    )
    (comp (ref "R36")
      (value "贴片电阻")
      (footprint "R0603")
      (description "Resistor")
      (fields (field (name "ALTIUM_VALUE") "10K 1%") (field (name "PUBLISHER") "Altium Limited"))
      (libsource (lib "Miscellaneous Devices") (part "Res1"))
    )
    (comp (ref "R37")
      (value "贴片电阻")
      (footprint "R0603")
      (description "Resistor")
      (fields (field (name "ALTIUM_VALUE") "10K 1%") (field (name "PUBLISHER") "Altium Limited"))
      (libsource (lib "Miscellaneous Devices") (part "Res1"))
    )
    (comp (ref "R38")
      (value "贴片电阻")
      (footprint "R0603")
      (description "Resistor")
      (fields (field (name "ALTIUM_VALUE") "10K 1%") (field (name "PUBLISHER") "Altium Limited"))
      (libsource (lib "Miscellaneous Devices") (part "Res1"))
    )
    (comp (ref "R39")
      (value "贴片电阻")
      (footprint "R0603")
      (description "Resistor")
      (fields (field (name "ALTIUM_VALUE") "10K 1%") (field (name "PUBLISHER") "Altium Limited"))
      (libsource (lib "Miscellaneous Devices") (part "Res1"))
    )
    (comp (ref "R40")
      (value "贴片电阻")
      (footprint "R0603")
      (description "Resistor")
      (fields (field (name "ALTIUM_VALUE") "1M 5%") (field (name "PUBLISHER") "Altium Limited"))
      (libsource (lib "Miscellaneous Devices") (part "Res1"))
    )
    (comp (ref "R41")
      (value "贴片电阻")
      (footprint "R0603")
      (description "Resistor")
      (fields (field (name "ALTIUM_VALUE") "1M 5%") (field (name "PUBLISHER") "Altium Limited"))
      (libsource (lib "Miscellaneous Devices") (part "Res1"))
    )
    (comp (ref "R42")
      (value "贴片电阻")
      (footprint "R0603")
      (description "Resistor")
      (fields (field (name "ALTIUM_VALUE") "10K 1%") (field (name "PUBLISHER") "Altium Limited"))
      (libsource (lib "Miscellaneous Devices") (part "Res1"))
    )
    (comp (ref "S1")
      (value "开关")
      (footprint "YT-8008-112A")
      (description "Single-Pole, Single-Throw Switch")
      (fields
        (field (name "ALTIUM_VALUE") "DC30V/1A YT-8008-112A")
        (field (name "PUBLISHER") "Altium Limited")
      )
      (libsource (lib "Miscellaneous Devices") (part "SW-SPST"))
    )
    (comp (ref "S2")
      (value "贴片轻触按钮")
      (footprint "Touch button")
      (description "Switch")
      (fields (field (name "ALTIUM_VALUE") "3.5*6*2.5mm") (field (name "PUBLISHER") "Altium Limited"))
      (libsource (lib "Miscellaneous Devices") (part "SW-PB"))
    )
    (comp (ref "S3")
      (value "开关")
      (footprint "DS-01")
      (description "Single-Pole, Single-Throw Switch")
      (fields (field (name "ALTIUM_VALUE") "DS-01") (field (name "PUBLISHER") "Altium Limited"))
      (libsource (lib "Miscellaneous Devices") (part "SW-SPST"))
    )
    (comp (ref "U1")
      (value "LS1C300B_176A")
      (footprint "QFP176")
      (description "龙芯1C300B QFP176A")
      (fields (field (name "ALTIUM_VALUE") "LS1C300B_176A"))
      (libsource (lib "LGHLIB") (part "LS1C300B_176A"))
    )
    (comp (ref "U2")
      (value "四通道单刀双掷模拟开关")
      (footprint "SOP-16")
      (description "四通道单刀双掷模拟开关 ，EN 低电平使能，IN 低电平 1#端导通，高电平2#端导通，DX是公共端")
      (fields (field (name "ALTIUM_VALUE") "CH440G"))
      (libsource (lib "LGHLIB") (part "CH440"))
    )
    (comp (ref "U3")
      (value "SDRAM")
      (footprint "TSOP54")
      (description "ISSI 公司SDRAM ， 166, 133, 100 MHz")
      (fields (field (name "ALTIUM_VALUE") "V54C3256164VHI6/IS42S16400-7T"))
      (libsource (lib "LGHLIB") (part "IS42S16400"))
    )
    (comp (ref "U4")
      (value "NOR FLASH")
      (footprint "SOIC-8-N")
      (description "nor flash W25Q64....华邦")
      (fields (field (name "ALTIUM_VALUE") "W25Q80"))
      (libsource (lib "LGHLIB") (part "W25Q80"))
    )
    (comp (ref "U5")
      (value "电源稳压芯片")
      (footprint "SOIC-8")
      (description "电源稳压芯片MPS,2A，18V的同步整流降压转换器")
      (fields (field (name "ALTIUM_VALUE") "MP1482DS"))
      (libsource (lib "LGHLIB") (part "MP1482"))
    )
    (comp (ref "U6")
      (value "通信芯片")
      (footprint "SOP28")
      (description "USB to Print Port / Parallel")
      (fields (field (name "ALTIUM_VALUE") "CH341A"))
      (libsource (lib "*") (part "CH341S_P"))
    )
    (comp (ref "U8")
      (value "电源稳压芯片")
      (footprint "SOIC-8")
      (description "电源稳压芯片MPS,2A，18V的同步整流降压转换器")
      (fields (field (name "ALTIUM_VALUE") "MP1482DS"))
      (libsource (lib "LGHLIB") (part "MP1482"))
    )
    (comp (ref "Y1")
      (value "直插晶振")
      (footprint "HC-49S")
      (description "Crystal Oscillator")
      (fields (field (name "ALTIUM_VALUE") "24MHz") (field (name "PUBLISHER") "Altium Limited"))
      (libsource (lib "Miscellaneous Devices") (part "XTAL"))
    )
    (comp (ref "Y2")
      (value "直插晶振")
      (footprint "TC-38")
      (description "Crystal Oscillator")
      (fields (field (name "ALTIUM_VALUE") "32.768KHz") (field (name "PUBLISHER") "Altium Limited"))
      (libsource (lib "Miscellaneous Devices") (part "XTAL"))
    )
    (comp (ref "Y3")
      (value "直插晶振")
      (footprint "HC-49S")
      (description "Crystal")
      (fields (field (name "ALTIUM_VALUE") "12MHz"))
      (libsource (lib "*") (part "CRYSTAL"))
    )
  )
  (nets
    (net (code "1") (name "/3") (class "Default")
      (node (ref "P1") (pin "3") (pinfunction "3_3") (pintype "passive"))
      (node (ref "U1") (pin "3") (pinfunction "LCD_CLK_/PIX_CLK/GPIO76_3") (pintype "passive"))
    )
    (net (code "2") (name "/4") (class "Default")
      (node (ref "P1") (pin "4") (pinfunction "4_4") (pintype "passive"))
      (node (ref "U1") (pin "4") (pinfunction "LCD_HSYNC_/GPIO74_/SPI0_CS1/__Sdio_Dat2__/UART0_RX_/PWM2_/I2C_SDA1_/SDRAM_CS1_4") (pintype "passive"))
    )
    (net (code "3") (name "/5") (class "Default")
      (node (ref "P1") (pin "5") (pinfunction "5_5") (pintype "passive"))
      (node (ref "U1") (pin "5") (pinfunction "LCD_VSYNC_/GPIO75_/SPI0_CS2/__Sdio_Dat3_/_UART0_TX_/PWM3_/I2C_SCL1_5") (pintype "passive"))
    )
    (net (code "4") (name "/6") (class "Default")
      (node (ref "P1") (pin "6") (pinfunction "6_6") (pintype "passive"))
      (node (ref "U1") (pin "6") (pinfunction "LCD_EN_/GPIO77_6") (pintype "passive"))
    )
    (net (code "5") (name "/7") (class "Default")
      (node (ref "P1") (pin "7") (pinfunction "7_7") (pintype "passive"))
      (node (ref "U1") (pin "7") (pinfunction "LCD_D0/LCD_B3/GPIO58_/UART4_RX/_UART0_CTS_7") (pintype "passive"))
    )
    (net (code "6") (name "/8") (class "Default")
      (node (ref "P1") (pin "8") (pinfunction "8_8") (pintype "passive"))
      (node (ref "U1") (pin "8") (pinfunction "LCD_D1/LCD_B4/GPIO59_/UART4_TX/_UART0_RTS_8") (pintype "passive"))
    )
    (net (code "7") (name "/9") (class "Default")
      (node (ref "P1") (pin "9") (pinfunction "9_9") (pintype "passive"))
      (node (ref "U1") (pin "9") (pinfunction "LCD_D2/LCD_B5/GPIO60_/UART5_RX/_UART0_DSR_9") (pintype "passive"))
    )
    (net (code "8") (name "/10") (class "Default")
      (node (ref "P1") (pin "10") (pinfunction "10_10") (pintype "passive"))
      (node (ref "U1") (pin "10") (pinfunction "LCD_D3/_LCD_B6_/GPIO61_/UART5_TX/_UART0_DTR_10") (pintype "passive"))
    )
    (net (code "9") (name "/12") (class "Default")
      (node (ref "P1") (pin "12") (pinfunction "12_12") (pintype "passive"))
      (node (ref "U1") (pin "12") (pinfunction "LCD_D4_/LCD_B7_/GPIO62_/UART6_RX/__UART0_DCD_12") (pintype "passive"))
    )
    (net (code "10") (name "/13") (class "Default")
      (node (ref "P1") (pin "13") (pinfunction "13_13") (pintype "passive"))
      (node (ref "U1") (pin "13") (pinfunction "LCD_D5_/LCD_G2_/GPIO63_/UART6_TX/UART0_RI_13") (pintype "passive"))
    )
    (net (code "11") (name "/14") (class "Default")
      (node (ref "P1") (pin "14") (pinfunction "14_14") (pintype "passive"))
      (node (ref "U1") (pin "14") (pinfunction "LCD_D6_/LCD_G3_/GPIO64_/UART7_RX_14") (pintype "passive"))
    )
    (net (code "12") (name "/15") (class "Default")
      (node (ref "P1") (pin "15") (pinfunction "15_15") (pintype "passive"))
      (node (ref "U1") (pin "15") (pinfunction "LCD_D7_/LCD_G4_/GPIO65_/UART7_TX_15") (pintype "passive"))
    )
    (net (code "13") (name "/16") (class "Default")
      (node (ref "P1") (pin "16") (pinfunction "16_16") (pintype "passive"))
      (node (ref "U1") (pin "16") (pinfunction "LCD_D8_/LCD_G5_/GPIO66_/UART8_RX_16") (pintype "passive"))
    )
    (net (code "14") (name "/17") (class "Default")
      (node (ref "P1") (pin "17") (pinfunction "17_17") (pintype "passive"))
      (node (ref "U1") (pin "17") (pinfunction "LCD_D9_/LCD_G6_/GPIO67_/UART8_TX_17") (pintype "passive"))
    )
    (net (code "15") (name "/19") (class "Default")
      (node (ref "P1") (pin "19") (pinfunction "19_19") (pintype "passive"))
      (node (ref "U1") (pin "19") (pinfunction "LCD_D10__/LCD_G7/_GPIO68_/UART9_RX/__UART8_CTS_19") (pintype "passive"))
    )
    (net (code "16") (name "/20") (class "Default")
      (node (ref "P1") (pin "20") (pinfunction "20_20") (pintype "passive"))
      (node (ref "U1") (pin "20") (pinfunction "LCD_R3__/LCD_D11_/GPIO69_/UART9_TX/__UART8_RTS_20") (pintype "passive"))
    )
    (net (code "17") (name "/21") (class "Default")
      (node (ref "P1") (pin "21") (pinfunction "21_21") (pintype "passive"))
      (node (ref "U1") (pin "21") (pinfunction "LCD_D12__/LCD_R4__/GPIO70_/UART10_RX/__UART8_DSR_21") (pintype "passive"))
    )
    (net (code "18") (name "/23") (class "Default")
      (node (ref "P1") (pin "22") (pinfunction "22_22") (pintype "passive"))
      (node (ref "U1") (pin "23") (pinfunction "LCD_D13_/LCD_R5__/GPIO71_/UART10_TX/__UART8_DTR_23") (pintype "passive"))
    )
    (net (code "19") (name "/24") (class "Default")
      (node (ref "P1") (pin "23") (pinfunction "23_23") (pintype "passive"))
      (node (ref "U1") (pin "24") (pinfunction "LCD_D14__/LCD_R6__/GPIO72_/UART11_RX/__UART8_DCD_24") (pintype "passive"))
    )
    (net (code "20") (name "/25") (class "Default")
      (node (ref "P1") (pin "24") (pinfunction "24_24") (pintype "passive"))
      (node (ref "U1") (pin "25") (pinfunction "LCD_D15__/LCD_R7__/GPIO73_/UART11_TX/__UART8_RI_25") (pintype "passive"))
    )
    (net (code "21") (name "/70") (class "Default")
      (node (ref "P4") (pin "2") (pinfunction "2_2") (pintype "passive"))
      (node (ref "U1") (pin "70") (pinfunction "I2S_DI_/GPIO87_/UART7_RX_70") (pintype "passive"))
    )
    (net (code "22") (name "/71") (class "Default")
      (node (ref "P4") (pin "3") (pinfunction "3_3") (pintype "passive"))
      (node (ref "U1") (pin "71") (pinfunction "I2S_DO_/GPIO88_/UART7_TX_71") (pintype "passive"))
    )
    (net (code "23") (name "/72") (class "Default")
      (node (ref "P4") (pin "4") (pinfunction "4_4") (pintype "passive"))
      (node (ref "U1") (pin "72") (pinfunction "I2S_LRCK_/GPIO89_/UART8_RX_72") (pintype "passive"))
    )
    (net (code "24") (name "/73") (class "Default")
      (node (ref "P4") (pin "5") (pinfunction "5_5") (pintype "passive"))
      (node (ref "U1") (pin "73") (pinfunction "I2S_BCLK_/GPIO90_/UART8_TX_73") (pintype "passive"))
    )
    (net (code "25") (name "/74") (class "Default")
      (node (ref "P4") (pin "6") (pinfunction "6_6") (pintype "passive"))
      (node (ref "U1") (pin "74") (pinfunction "I2C_SDA0_/GPIO85_/UART9_RX/__UART8_CTS_74") (pintype "passive"))
    )
    (net (code "26") (name "/75") (class "Default")
      (node (ref "P4") (pin "7") (pinfunction "7_7") (pintype "passive"))
      (node (ref "U1") (pin "75") (pinfunction "I2C_SCL0__/GPIO86_/UART9_TX/__UART8_RTS_75") (pintype "passive"))
    )
    (net (code "27") (name "/76") (class "Default")
      (node (ref "P4") (pin "8") (pinfunction "8_8") (pintype "passive"))
      (node (ref "U1") (pin "76") (pinfunction "I2S_MCLK_/GPIO91_76") (pintype "passive"))
    )
    (net (code "28") (name "/77") (class "Default")
      (node (ref "P4") (pin "9") (pinfunction "9_9") (pintype "passive"))
      (node (ref "U1") (pin "77") (pinfunction "PWM1_/GPIO92_/ADC_YN_77") (pintype "passive"))
    )
    (net (code "29") (name "/78") (class "Default")
      (node (ref "P4") (pin "10") (pinfunction "10_10") (pintype "passive"))
      (node (ref "U1") (pin "78") (pinfunction "PWM0/__CAMCLKOUT__/GPIO06_/ADC_XN_78") (pintype "passive"))
    )
    (net (code "30") (name "/79") (class "Default")
      (node (ref "P4") (pin "11") (pinfunction "11_11") (pintype "passive"))
      (node (ref "U1") (pin "79") (pinfunction "SPI0_CS2_/GPIO83_/Sdio_Dat3_79") (pintype "passive"))
    )
    (net (code "31") (name "/82") (class "Default")
      (node (ref "P4") (pin "14") (pinfunction "14_14") (pintype "passive"))
      (node (ref "U1") (pin "82") (pinfunction "ADC_VREF_82") (pintype "passive"))
    )
    (net (code "32") (name "/85") (class "Default")
      (node (ref "P4") (pin "15") (pinfunction "15_15") (pintype "passive"))
      (node (ref "U1") (pin "85") (pinfunction "ADC_D0_85") (pintype "passive"))
    )
    (net (code "33") (name "/86") (class "Default")
      (node (ref "P4") (pin "16") (pinfunction "16_16") (pintype "passive"))
      (node (ref "U1") (pin "86") (pinfunction "ADC_D1_86") (pintype "passive"))
    )
    (net (code "34") (name "/87") (class "Default")
      (node (ref "P4") (pin "17") (pinfunction "17_17") (pintype "passive"))
      (node (ref "U1") (pin "87") (pinfunction "ADC_XP_87") (pintype "passive"))
    )
    (net (code "35") (name "/88") (class "Default")
      (node (ref "P4") (pin "18") (pinfunction "18_18") (pintype "passive"))
      (node (ref "U1") (pin "88") (pinfunction "ADC_YP_88") (pintype "passive"))
    )
    (net (code "36") (name "/89") (class "Default")
      (node (ref "P4") (pin "19") (pinfunction "19_19") (pintype "passive"))
      (node (ref "U1") (pin "89") (pinfunction "SPI0_CS3_/GPIO84_/CAMCLKOUT_/UART10_RX/__UART8_DSR_89") (pintype "passive"))
    )
    (net (code "37") (name "/93") (class "Default")
      (node (ref "P4") (pin "20") (pinfunction "20_20") (pintype "passive"))
      (node (ref "U1") (pin "93") (pinfunction "SPI0_CS1_/GPIO82_/Sdio_Dat2_/UART10_TX/__UART8_DTR_93") (pintype "passive"))
    )
    (net (code "38") (name "/103") (class "Default")
      (node (ref "P4") (pin "23") (pinfunction "23_23") (pintype "passive"))
      (node (ref "U1") (pin "103") (pinfunction "CAMDATA7_/GPIO57_/LCD_R2_/CAN1_TX_/I2C_SCL2_/UART7_RX_103") (pintype "passive"))
    )
    (net (code "39") (name "/104") (class "Default")
      (node (ref "P4") (pin "24") (pinfunction "24_24") (pintype "passive"))
      (node (ref "U1") (pin "104") (pinfunction "CAMDATA6_/GPIO56_/LCD_R1_/CAN1_RX_/I2C_SDA2_/UART7_TX_104") (pintype "passive"))
    )
    (net (code "40") (name "/105") (class "Default")
      (node (ref "P4") (pin "25") (pinfunction "25_25") (pintype "passive"))
      (node (ref "U1") (pin "105") (pinfunction "CAMDATA5_/GPIO55_/LCD_R0_/CAN0_TX_/I2C_SCL1_/UART8_RX_105") (pintype "passive"))
    )
    (net (code "41") (name "/106") (class "Default")
      (node (ref "P4") (pin "26") (pinfunction "26_26") (pintype "passive"))
      (node (ref "U1") (pin "106") (pinfunction "CAMDATA4_/GPIO54_/LCD_G1_/CAN0_RX_/I2C_SDA1_/UART8_TX_106") (pintype "passive"))
    )
    (net (code "42") (name "/107") (class "Default")
      (node (ref "P4") (pin "27") (pinfunction "27_27") (pintype "passive"))
      (node (ref "U1") (pin "107") (pinfunction "CAMDATA3_/GPIO53_/LCD_G0_/CAMCLKOUT_/PWM3_/UART9_RX/__UART8_CTS_107") (pintype "passive"))
    )
    (net (code "43") (name "/108") (class "Default")
      (node (ref "P4") (pin "28") (pinfunction "28_28") (pintype "passive"))
      (node (ref "U1") (pin "108") (pinfunction "CAMDATA2_/GPIO52_/LCD_B2_/SPI1_CS3_/PWM2_/UART9_TX/__UART8_RTS_108") (pintype "passive"))
    )
    (net (code "44") (name "/109") (class "Default")
      (node (ref "P6") (pin "13") (pinfunction "13_13") (pintype "passive"))
      (node (ref "U1") (pin "109") (pinfunction "CAMDATA1_/GPIO51_/LCD_B1_/SPI1_CS2_/I2C_SCL2_/UART10_RX/__UART8_DSR_109") (pintype "passive"))
    )
    (net (code "45") (name "/110") (class "Default")
      (node (ref "P6") (pin "14") (pinfunction "14_14") (pintype "passive"))
      (node (ref "U1") (pin "110") (pinfunction "CAMDATA0_/GPIO50_/LCD_B0_/SPI1_CS1_/I2C_SDA2_/UART10_TX/__UART8_DTR_110") (pintype "passive"))
    )
    (net (code "46") (name "/112") (class "Default")
      (node (ref "P6") (pin "12") (pinfunction "12_12") (pintype "passive"))
      (node (ref "U1") (pin "112") (pinfunction "CAMHSYNC_/GPIO49_/NAND_RDY3_/SPI1_CS0_/I2C_SCL1_/UART11_RX/__UART8_DCD_112") (pintype "passive"))
    )
    (net (code "47") (name "/113") (class "Default")
      (node (ref "P6") (pin "9") (pinfunction "9_9") (pintype "passive"))
      (node (ref "U1") (pin "113") (pinfunction "CAMVSYNC_/GPIO48_/NAND_CE#3_/SPI1_MOSI_/I2C_SDA1_/UART11_TX/__UART8_RI_113") (pintype "passive"))
    )
    (net (code "48") (name "/114") (class "Default")
      (node (ref "P6") (pin "10") (pinfunction "10_10") (pintype "passive"))
      (node (ref "U1") (pin "114") (pinfunction "CAMCLKOUT_/GPIO47_/SRAM_A25_/NAND_RDY2_/SPI1_MISO_/PWM3_/UART6_RX/__UART0_DCD_114") (pintype "passive"))
    )
    (net (code "49") (name "/115") (class "Default")
      (node (ref "P6") (pin "7") (pinfunction "7_7") (pintype "passive"))
      (node (ref "U1") (pin "115") (pinfunction "CAMPCLKIN_/GPIO46_/SRAM_A24_/NAND_CE#2_/SPI1_CLK_/PWM2_/UART6_TX/__UART0_RI_115") (pintype "passive"))
    )
    (net (code "50") (name "/116") (class "Default")
      (node (ref "P6") (pin "8") (pinfunction "8_8") (pintype "passive"))
      (node (ref "U1") (pin "116") (pinfunction "NAND_7_/GPIO20_/SPI1_CS1/__Sdio_Dat2__/MAC_MDIO_/CAMDATA0_/I2C_SCL2_116") (pintype "passive"))
    )
    (net (code "51") (name "/117") (class "Default")
      (node (ref "P6") (pin "5") (pinfunction "5_5") (pintype "passive"))
      (node (ref "U1") (pin "117") (pinfunction "NAND_6_/GPIO19_/SPI1_CS2/__Sdio_Dat3__/MAC_MDC_/CAMDATA1_/I2C_SDA2_117") (pintype "passive"))
    )
    (net (code "52") (name "/118(5)") (class "Default")
      (node (ref "P6") (pin "6") (pinfunction "6_6") (pintype "passive"))
      (node (ref "R16") (pin "2") (pinfunction "2_2") (pintype "passive"))
      (node (ref "U1") (pin "118") (pinfunction "NAND_5_/GPIO18_/UART1_TX_/UART3_TX_/CAMDATA2_/PWM2_118") (pintype "passive"))
    )
    (net (code "53") (name "/119(4)") (class "Default")
      (node (ref "P6") (pin "3") (pinfunction "3_3") (pintype "passive"))
      (node (ref "R15") (pin "2") (pinfunction "2_2") (pintype "passive"))
      (node (ref "U1") (pin "119") (pinfunction "NAND_4_/GPIO17_/UART1_RX_/UART3_RX_/CAMDATA3_/PWM3_119") (pintype "passive"))
    )
    (net (code "54") (name "/120") (class "Default")
      (node (ref "P6") (pin "4") (pinfunction "4_4") (pintype "passive"))
      (node (ref "U1") (pin "120") (pinfunction "NAND_3_/GPIO16_/SPI1_CS0/__Sdio_Dat1__/CAN1_TX_/CAMDATA4_/I2S_LRCK_120") (pintype "passive"))
    )
    (net (code "55") (name "/121") (class "Default")
      (node (ref "P6") (pin "1") (pinfunction "1_1") (pintype "passive"))
      (node (ref "U1") (pin "121") (pinfunction "NAND_2_/GPIO15_/SPI1_MOSI/__Sdio_Dat0/CAN1_RX_/CAMDATA5_/I2S_DO_121") (pintype "passive"))
    )
    (net (code "56") (name "/122") (class "Default")
      (node (ref "P6") (pin "2") (pinfunction "2_2") (pintype "passive"))
      (node (ref "U1") (pin "122") (pinfunction "NAND_1_/GPIO14_/SPI1_MISO/__Sdio_Cmd__/CAN0_TX_/CAMDATA6_/I2S_BCLK_122") (pintype "passive"))
    )
    (net (code "57") (name "/123") (class "Default")
      (node (ref "P3") (pin "13") (pinfunction "13_13") (pintype "passive"))
      (node (ref "U1") (pin "123") (pinfunction "NAND_0_/GPIO13_/SPI1_CLK/__Sdio_clk__/CAN0_RX_/CAMDATA7_/I2S_MCLK_/GPIO_123") (pintype "passive"))
    )
    (net (code "58") (name "/127") (class "Default")
      (node (ref "P3") (pin "9") (pinfunction "9_9") (pintype "passive"))
      (node (ref "U1") (pin "127") (pinfunction "NAND_RDY_/GPIO07_127") (pintype "passive"))
    )
    (net (code "59") (name "/128") (class "Default")
      (node (ref "P3") (pin "10") (pinfunction "10_10") (pintype "passive"))
      (node (ref "U1") (pin "128") (pinfunction "NAND_CLE_/GPIO08_/GPIO_128") (pintype "passive"))
    )
    (net (code "60") (name "/129") (class "Default")
      (node (ref "P3") (pin "7") (pinfunction "7_7") (pintype "passive"))
      (node (ref "U1") (pin "129") (pinfunction "NAND_ALE_/GPIO09_/GPIO_129") (pintype "passive"))
    )
    (net (code "61") (name "/130") (class "Default")
      (node (ref "P3") (pin "8") (pinfunction "8_8") (pintype "passive"))
      (node (ref "U1") (pin "130") (pinfunction "NAND_RD#_/GPIO10_/GPIO_130") (pintype "passive"))
    )
    (net (code "62") (name "/132") (class "Default")
      (node (ref "P3") (pin "6") (pinfunction "6_6") (pintype "passive"))
      (node (ref "U1") (pin "132") (pinfunction "NAND_CE#_/GPIO11_/GPIO_132") (pintype "passive"))
    )
    (net (code "63") (name "/133") (class "Default")
      (node (ref "P3") (pin "3") (pinfunction "3_3") (pintype "passive"))
      (node (ref "U1") (pin "133") (pinfunction "NAND_WR#_/GPIO12_/GPIO_133") (pintype "passive"))
    )
    (net (code "64") (name "/134") (class "Default")
      (node (ref "P3") (pin "4") (pinfunction "4_4") (pintype "passive"))
      (node (ref "U1") (pin "134") (pinfunction "MAC_TXEN_/GPIO21_/I2S_MCLK_/NAND_CLE_/I2C_SDA2_/CAN0_RX_/UART8_RX_134") (pintype "passive"))
    )
    (net (code "65") (name "/135") (class "Default")
      (node (ref "P3") (pin "1") (pinfunction "1_1") (pintype "passive"))
      (node (ref "U1") (pin "135") (pinfunction "MAC_TXD0_/GPIO23_/I2S_DO_/NAND_ALE_/UART0_RX_/CAN1_RX_/UART4_RX/__UART0_CTS_135") (pintype "passive"))
    )
    (net (code "66") (name "/136") (class "Default")
      (node (ref "P3") (pin "2") (pinfunction "2_2") (pintype "passive"))
      (node (ref "U1") (pin "136") (pinfunction "MAC_TXD1_/GPIO24_/I2S_LRCK_/NAND_WR#_/UART0_TX_/CAN1_TX_/UART4_TX/__UART0_RTS_136") (pintype "passive"))
    )
    (net (code "67") (name "/137") (class "Default")
      (node (ref "P2") (pin "27") (pinfunction "27_27") (pintype "passive"))
      (node (ref "U1") (pin "137") (pinfunction "MAC_RXER_/GPIO25_/I2S_DI_/NAND_RDY0_/I2C_SDA1_/CAMCLKOUT_/UART5_RX/__UART0_DSR_137") (pintype "passive"))
    )
    (net (code "68") (name "/138") (class "Default")
      (node (ref "P2") (pin "28") (pinfunction "28_28") (pintype "passive"))
      (node (ref "U1") (pin "138") (pinfunction "MAC_RXDV_/GPIO26_/SPI1_CS3_/NAND_CE#0_/I2C_SCL1_/CAMPCLKIN_/UART5_TX/__UART0_DTR__/GPIO_138") (pintype "passive"))
    )
    (net (code "69") (name "/139") (class "Default")
      (node (ref "P2") (pin "25") (pinfunction "25_25") (pintype "passive"))
      (node (ref "U1") (pin "139") (pinfunction "MAC_RXD0_/GPIO27_/I2C_SDA_/PWM2_/UART2_RX_/CAMVSYNC_/UART6_RX/__UART0_DCD__/GPIO_139") (pintype "passive"))
    )
    (net (code "70") (name "/140") (class "Default")
      (node (ref "P2") (pin "26") (pinfunction "26_26") (pintype "passive"))
      (node (ref "U1") (pin "140") (pinfunction "MAC_RXD1_/GPIO28_/I2C_SCL_/PWM3_/UART2_TX_/CAMHSYNC_/UART6_TX/__UART0_RI__/GPIO_140") (pintype "passive"))
    )
    (net (code "71") (name "/141") (class "Default")
      (node (ref "P2") (pin "23") (pinfunction "23_23") (pintype "passive"))
      (node (ref "U1") (pin "141") (pinfunction "MAC_MDC_/GPIO29_/CAMDATA7_/NAND_CE#1_/PWM2_/I2C_SCL1_/UART8_TX_/GPIO_141") (pintype "passive"))
    )
    (net (code "72") (name "/143") (class "Default")
      (node (ref "P2") (pin "21") (pinfunction "21_21") (pintype "passive"))
      (node (ref "U1") (pin "143") (pinfunction "MAC_MDIO_/GPIO30_/CAMDATA6_/NAND_RDY1_/LCD_B0_/I2C_SDA1_/GPIO_143") (pintype "passive"))
    )
    (net (code "73") (name "/144") (class "Default")
      (node (ref "P2") (pin "22") (pinfunction "22_22") (pintype "passive"))
      (node (ref "U1") (pin "144") (pinfunction "MAC_RXD2_/GPIO31_/CAMDATA5_/NAND_CS#2_/LCD_B1_/CAN1_RX_/UART11_RX/__UART8_DCD__/GPIO_144") (pintype "passive"))
    )
    (net (code "74") (name "/145") (class "Default")
      (node (ref "D3") (pin "2") (pinfunction "K_2") (pintype "passive"))
      (node (ref "P2") (pin "19") (pinfunction "19_19") (pintype "passive"))
      (node (ref "U1") (pin "145") (pinfunction "MAC_TXD2_/GPIO32_/CAMDATA4_/NAND_RDY2_/LCD_B2_/CAN1_TX_/UART11_TX/__UART8_RI_145") (pintype "passive"))
    )
    (net (code "75") (name "/146") (class "Default")
      (node (ref "P2") (pin "20") (pinfunction "20_20") (pintype "passive"))
      (node (ref "U1") (pin "146") (pinfunction "MAC_RXD3_/GPIO33_/CAMDATA3_/UART3_RX_/LCD_G0_/SPI1_CLK/__Sdio_clk_146") (pintype "passive"))
    )
    (net (code "76") (name "/147") (class "Default")
      (node (ref "P2") (pin "17") (pinfunction "17_17") (pintype "passive"))
      (node (ref "U1") (pin "147") (pinfunction "MAC_TXD3_/GPIO34_/CAMDATA2_/UART3_TX_/LCD_G1_/SPI1_MISO/__Sdio_Cmd_147") (pintype "passive"))
    )
    (net (code "77") (name "/148") (class "Default")
      (node (ref "P2") (pin "18") (pinfunction "18_18") (pintype "passive"))
      (node (ref "U1") (pin "148") (pinfunction "MAC_TXC_/GPIO22_/I2S_BCLK_/NAND_RD#_/I2C_SCL2_/CANO_TX_/SDRAM_CS1_148") (pintype "passive"))
    )
    (net (code "78") (name "/151") (class "Default")
      (node (ref "P2") (pin "13") (pinfunction "13_13") (pintype "passive"))
      (node (ref "U1") (pin "151") (pinfunction "MAC_CRS__(ONLY_MII)_/GPIO35_/CAMDATA1_/PWM1_/LCD_R0_/SPI1_MOSI/__Sdio_Dat0_151") (pintype "passive"))
    )
    (net (code "79") (name "/157") (class "Default")
      (node (ref "P2") (pin "11") (pinfunction "11_11") (pintype "passive"))
      (node (ref "U1") (pin "157") (pinfunction "OTG_DM_157") (pintype "passive"))
    )
    (net (code "80") (name "/158") (class "Default")
      (node (ref "P2") (pin "10") (pinfunction "10_10") (pintype "passive"))
      (node (ref "U1") (pin "158") (pinfunction "OTG_DP_158") (pintype "passive"))
    )
    (net (code "81") (name "/160") (class "Default")
      (node (ref "P2") (pin "8") (pinfunction "8_8") (pintype "passive"))
      (node (ref "U1") (pin "160") (pinfunction "OTG_VBUS_160") (pintype "passive"))
    )
    (net (code "82") (name "/161") (class "Default")
      (node (ref "P2") (pin "7") (pinfunction "7_7") (pintype "passive"))
      (node (ref "U1") (pin "161") (pinfunction "OTG_ID_161") (pintype "passive"))
    )
    (net (code "83") (name "/168") (class "Default")
      (node (ref "P2") (pin "6") (pinfunction "6_6") (pintype "passive"))
      (node (ref "U1") (pin "168") (pinfunction "USB_DM_168") (pintype "passive"))
    )
    (net (code "84") (name "/169") (class "Default")
      (node (ref "P2") (pin "3") (pinfunction "3_3") (pintype "passive"))
      (node (ref "U1") (pin "169") (pinfunction "USB_DP_169") (pintype "passive"))
    )
    (net (code "85") (name "/CH_CLK_SPI0_CLK") (class "Default")
      (node (ref "U2") (pin "2") (pinfunction "S1A_2") (pintype "passive"))
      (node (ref "U6") (pin "18") (pinfunction "D3_18") (pintype "bidirectional"))
    )
    (net (code "86") (name "/CH_MISO_SPI0_MISO") (class "Default")
      (node (ref "U2") (pin "11") (pinfunction "S1C_11") (pintype "passive"))
      (node (ref "U6") (pin "22") (pinfunction "D7_22") (pintype "bidirectional"))
    )
    (net (code "87") (name "/CH_MOSI_SPI0_MOSI") (class "Default")
      (node (ref "U2") (pin "5") (pinfunction "S1B_5") (pintype "passive"))
      (node (ref "U6") (pin "20") (pinfunction "D5_20") (pintype "bidirectional"))
    )
    (net (code "88") (name "/CH_SDA") (class "Default")
      (node (ref "R42") (pin "1") (pinfunction "1_1") (pintype "passive"))
      (node (ref "S3") (pin "2") (pinfunction "NO_2") (pintype "passive"))
      (node (ref "U2") (pin "1") (pinfunction "IN_1") (pintype "passive"))
      (node (ref "U6") (pin "23") (pinfunction "SDA_23") (pintype "bidirectional"))
    )
    (net (code "89") (name "/D+") (class "Default")
      (node (ref "P8") (pin "A6") (pinfunction "DP1_A6") (pintype "passive"))
      (node (ref "P8") (pin "B6") (pinfunction "DP2_B6") (pintype "passive"))
      (node (ref "U6") (pin "10") (pinfunction "UD+_10") (pintype "bidirectional"))
    )
    (net (code "90") (name "/D-") (class "Default")
      (node (ref "P8") (pin "A7") (pinfunction "DN1_A7") (pintype "passive"))
      (node (ref "P8") (pin "B7") (pinfunction "DN2_B7") (pintype "passive"))
      (node (ref "U6") (pin "11") (pinfunction "UD-_11") (pintype "bidirectional"))
    )
    (net (code "91") (name "/EJTAG_RST") (class "Default")
      (node (ref "P5") (pin "1") (pinfunction "TRST_N_1") (pintype "passive"))
      (node (ref "R35") (pin "1") (pinfunction "1_1") (pintype "passive"))
      (node (ref "U1") (pin "100") (pinfunction "EJTAG_RST_/GPIO05_/CAMDATA0_/I2C_SCL2_/PWM1_/UART2_TX_/GPIO_100") (pintype "passive"))
    )
    (net (code "92") (name "/EJTAG_SEL") (class "Default")
      (node (ref "R38") (pin "1") (pinfunction "1_1") (pintype "passive"))
      (node (ref "R39") (pin "1") (pinfunction "1_1") (pintype "passive"))
      (node (ref "U1") (pin "95") (pinfunction "EJTAG_SEL_/GPIO00_/CAMCLKOUT_/I2C_SDA0_/CAN0_RX_/UART3_RX_/SDRAM_CS1_/GPIO_95") (pintype "passive"))
    )
    (net (code "93") (name "/EJTAG_TCK") (class "Default")
      (node (ref "P5") (pin "5") (pinfunction "TCK_5") (pintype "passive"))
      (node (ref "R30") (pin "1") (pinfunction "1_1") (pintype "passive"))
      (node (ref "U1") (pin "96") (pinfunction "EJTAG_TCK_/GPIO01_/CAMPCLKIN_/I2C_SCL0_/CAN0_TX_/UART3_TX_/GPIO_96") (pintype "passive"))
    )
    (net (code "94") (name "/EJTAG_TDI") (class "Default")
      (node (ref "P5") (pin "2") (pinfunction "TDI_2") (pintype "passive"))
      (node (ref "R33") (pin "1") (pinfunction "1_1") (pintype "passive"))
      (node (ref "R34") (pin "1") (pinfunction "1_1") (pintype "passive"))
      (node (ref "U1") (pin "99") (pinfunction "EJTAG_TDI_/GPIO02_/CAMVSYNC_/I2C_SDA1_/CAN1_RX_/UART1_RX_/GPIO_99") (pintype "passive"))
    )
    (net (code "95") (name "/EJTAG_TDO") (class "Default")
      (node (ref "P5") (pin "3") (pinfunction "TDO_3") (pintype "passive"))
      (node (ref "R32") (pin "1") (pinfunction "1_1") (pintype "passive"))
      (node (ref "U1") (pin "98") (pinfunction "EJTAG_TDO_/GPIO03_/CAMHSYNC_/I2C_SCL1_/CAN1_TX_/UART1_TX_/GPIO_98") (pintype "passive"))
    )
    (net (code "96") (name "/EJTAG_TMS") (class "Default")
      (node (ref "P5") (pin "4") (pinfunction "TMS_4") (pintype "passive"))
      (node (ref "R31") (pin "1") (pinfunction "1_1") (pintype "passive"))
      (node (ref "U1") (pin "97") (pinfunction "EJTAG_TMS_/GPIO04_/CAMDATA1_/I2C_SDA2_/PWM0_/UART2_RX_/GPIO_97") (pintype "passive"))
    )
    (net (code "97") (name "/FLASH_CS0") (class "Default")
      (node (ref "R6") (pin "2") (pinfunction "2_2") (pintype "passive"))
      (node (ref "U2") (pin "12") (pinfunction "DD_12") (pintype "passive"))
      (node (ref "U4") (pin "1") (pinfunction "~{CS}_1") (pintype "passive"))
    )
    (net (code "98") (name "/JTAG_SEL") (class "Default")
      (node (ref "P5") (pin "7") (pinfunction "NC_7") (pintype "passive"))
      (node (ref "R36") (pin "1") (pinfunction "1_1") (pintype "passive"))
      (node (ref "R37") (pin "1") (pinfunction "1_1") (pintype "passive"))
      (node (ref "U1") (pin "126") (pinfunction "JTAG_SEL_/SDRAM_CS1_/UART6_TX/__UART0_RI_126") (pintype "passive"))
    )
    (net (code "99") (name "/RTCI") (class "Default")
      (node (ref "C3") (pin "2") (pinfunction "2_2") (pintype "passive"))
      (node (ref "R41") (pin "2") (pinfunction "2_2") (pintype "passive"))
      (node (ref "U1") (pin "175") (pinfunction "RTC_CLK_I_175") (pintype "passive"))
      (node (ref "Y2") (pin "2") (pinfunction "OSC2_2") (pintype "passive"))
    )
    (net (code "100") (name "/RTCO") (class "Default")
      (node (ref "C4") (pin "2") (pinfunction "2_2") (pintype "passive"))
      (node (ref "R41") (pin "1") (pinfunction "1_1") (pintype "passive"))
      (node (ref "U1") (pin "174") (pinfunction "RTC_CLK_O_174") (pintype "passive"))
      (node (ref "Y2") (pin "1") (pinfunction "OSC1_1") (pintype "passive"))
    )
    (net (code "101") (name "/RTC_VDDA") (class "Default")
      (node (ref "D1") (pin "2") (pinfunction "K_2") (pintype "passive"))
      (node (ref "P2") (pin "4") (pinfunction "4_4") (pintype "passive"))
      (node (ref "U1") (pin "176") (pinfunction "RTC_VR_VDDA_176") (pintype "passive"))
    )
    (net (code "102") (name "/SDRAM_A0") (class "Default")
      (node (ref "U1") (pin "67") (pinfunction "SD_A00/__SRAM_A00_67") (pintype "passive"))
      (node (ref "U3") (pin "23") (pinfunction "A0_23") (pintype "passive"))
    )
    (net (code "103") (name "/SDRAM_A1") (class "Default")
      (node (ref "U1") (pin "66") (pinfunction "SD_A01/__SRAM_A01_66") (pintype "passive"))
      (node (ref "U3") (pin "24") (pinfunction "A1_24") (pintype "passive"))
    )
    (net (code "104") (name "/SDRAM_A2") (class "Default")
      (node (ref "U1") (pin "65") (pinfunction "SD_A02/__SRAM_A02_65") (pintype "passive"))
      (node (ref "U3") (pin "25") (pinfunction "A2_25") (pintype "passive"))
    )
    (net (code "105") (name "/SDRAM_A3") (class "Default")
      (node (ref "U1") (pin "64") (pinfunction "SD_A03/__SRAM_A03_64") (pintype "passive"))
      (node (ref "U3") (pin "26") (pinfunction "A3_26") (pintype "passive"))
    )
    (net (code "106") (name "/SDRAM_A4") (class "Default")
      (node (ref "U1") (pin "63") (pinfunction "SD_A04/__SRAM_A04_63") (pintype "passive"))
      (node (ref "U3") (pin "29") (pinfunction "A4_29") (pintype "passive"))
    )
    (net (code "107") (name "/SDRAM_A5") (class "Default")
      (node (ref "U1") (pin "62") (pinfunction "SD_A05/__SRAM_A05_62") (pintype "passive"))
      (node (ref "U3") (pin "30") (pinfunction "A5_30") (pintype "passive"))
    )
    (net (code "108") (name "/SDRAM_A6") (class "Default")
      (node (ref "U1") (pin "61") (pinfunction "SD_A06/__SRAM_A06_61") (pintype "passive"))
      (node (ref "U3") (pin "31") (pinfunction "A6_31") (pintype "passive"))
    )
    (net (code "109") (name "/SDRAM_A7") (class "Default")
      (node (ref "U1") (pin "60") (pinfunction "SD_A07/__SRAM_A07_60") (pintype "passive"))
      (node (ref "U3") (pin "32") (pinfunction "A7_32") (pintype "passive"))
    )
    (net (code "110") (name "/SDRAM_A8") (class "Default")
      (node (ref "U1") (pin "59") (pinfunction "SD_A08/__SRAM_A08_59") (pintype "passive"))
      (node (ref "U3") (pin "33") (pinfunction "A8_33") (pintype "passive"))
    )
    (net (code "111") (name "/SDRAM_A9") (class "Default")
      (node (ref "U1") (pin "58") (pinfunction "SD_A09/__SRAM_A09_58") (pintype "passive"))
      (node (ref "U3") (pin "34") (pinfunction "A9_34") (pintype "passive"))
    )
    (net (code "112") (name "/SDRAM_A10") (class "Default")
      (node (ref "U1") (pin "57") (pinfunction "SD_A10/__SRAM_A10_57") (pintype "passive"))
      (node (ref "U3") (pin "22") (pinfunction "A10_22") (pintype "passive"))
    )
    (net (code "113") (name "/SDRAM_A11") (class "Default")
      (node (ref "U1") (pin "56") (pinfunction "SD_A11/__SRAM_A11_56") (pintype "passive"))
      (node (ref "U3") (pin "35") (pinfunction "A11_35") (pintype "passive"))
    )
    (net (code "114") (name "/SDRAM_A12") (class "Default")
      (node (ref "U1") (pin "55") (pinfunction "SD_A12/__SRAM_A12_55") (pintype "passive"))
      (node (ref "U3") (pin "36") (pinfunction "NC_36") (pintype "passive"))
    )
    (net (code "115") (name "/SDRAM_BA0") (class "Default")
      (node (ref "U1") (pin "52") (pinfunction "SD_BA0/__SRAM_A17_52") (pintype "passive"))
      (node (ref "U3") (pin "20") (pinfunction "BA0_20") (pintype "passive"))
    )
    (net (code "116") (name "/SDRAM_BA1") (class "Default")
      (node (ref "U1") (pin "50") (pinfunction "SD_BA1/__SRAM_A16_50") (pintype "passive"))
      (node (ref "U3") (pin "21") (pinfunction "BA1_21") (pintype "passive"))
    )
    (net (code "117") (name "/SDRAM_CKE") (class "Default")
      (node (ref "U1") (pin "53") (pinfunction "SD_CKE/__SRAM_A13_53") (pintype "passive"))
      (node (ref "U3") (pin "37") (pinfunction "CKE_37") (pintype "passive"))
    )
    (net (code "118") (name "/SDRAM_CLK") (class "Default")
      (node (ref "U1") (pin "54") (pinfunction "SD_CLK/__SRAM_OEn_54") (pintype "passive"))
      (node (ref "U3") (pin "38") (pinfunction "CLK_38") (pintype "passive"))
    )
    (net (code "119") (name "/SDRAM_D0") (class "Default")
      (node (ref "U1") (pin "44") (pinfunction "SD_D00/__SRAM_D00_44") (pintype "passive"))
      (node (ref "U3") (pin "2") (pinfunction "I/O0_2") (pintype "passive"))
    )
    (net (code "120") (name "/SDRAM_D1") (class "Default")
      (node (ref "U1") (pin "43") (pinfunction "SD_D01/__SRAM_D01_43") (pintype "passive"))
      (node (ref "U3") (pin "4") (pinfunction "I/O1_4") (pintype "passive"))
    )
    (net (code "121") (name "/SDRAM_D2") (class "Default")
      (node (ref "U1") (pin "42") (pinfunction "SD_D02/__SRAM_D02_42") (pintype "passive"))
      (node (ref "U3") (pin "5") (pinfunction "I/O2_5") (pintype "passive"))
    )
    (net (code "122") (name "/SDRAM_D3") (class "Default")
      (node (ref "U1") (pin "41") (pinfunction "SD_D03/__SRAM_D03_41") (pintype "passive"))
      (node (ref "U3") (pin "7") (pinfunction "I/O3_7") (pintype "passive"))
    )
    (net (code "123") (name "/SDRAM_D4") (class "Default")
      (node (ref "U1") (pin "40") (pinfunction "SD_D04/__SRAM_D04_40") (pintype "passive"))
      (node (ref "U3") (pin "8") (pinfunction "I/O4_8") (pintype "passive"))
    )
    (net (code "124") (name "/SDRAM_D5") (class "Default")
      (node (ref "U1") (pin "39") (pinfunction "SD_D05/__SRAM_D05_39") (pintype "passive"))
      (node (ref "U3") (pin "10") (pinfunction "I/O5_10") (pintype "passive"))
    )
    (net (code "125") (name "/SDRAM_D6") (class "Default")
      (node (ref "U1") (pin "38") (pinfunction "SD_D06/__SRAM_D06_38") (pintype "passive"))
      (node (ref "U3") (pin "11") (pinfunction "I/O6_11") (pintype "passive"))
    )
    (net (code "126") (name "/SDRAM_D7") (class "Default")
      (node (ref "U1") (pin "37") (pinfunction "SD_D07/__SRAM_D07_37") (pintype "passive"))
      (node (ref "U3") (pin "13") (pinfunction "I/O7_13") (pintype "passive"))
    )
    (net (code "127") (name "/SDRAM_D8") (class "Default")
      (node (ref "U1") (pin "34") (pinfunction "SD_D08/__SRAM_D08_/GPIO97_/I2S_MCLK_/NAND_CLE_/I2C_SDA2_/CAN0_RX_34") (pintype "passive"))
      (node (ref "U3") (pin "42") (pinfunction "I/O8_42") (pintype "passive"))
    )
    (net (code "128") (name "/SDRAM_D9") (class "Default")
      (node (ref "U1") (pin "33") (pinfunction "SD_D09/__SRAM_D09_/GPIO98_/I2S_BCLK_/NAND_RD#_/I2C_SCL2_/CANO_TX_33") (pintype "passive"))
      (node (ref "U3") (pin "44") (pinfunction "I/O9_44") (pintype "passive"))
    )
    (net (code "129") (name "/SDRAM_D10") (class "Default")
      (node (ref "U1") (pin "32") (pinfunction "SD_D10/__SRAM_D10__/GPIO99_/I2S_DI_/NAND_ALE_/UART0_RX_/CAN1_RX_32") (pintype "passive"))
      (node (ref "U3") (pin "45") (pinfunction "I/O10_45") (pintype "passive"))
    )
    (net (code "130") (name "/SDRAM_D11") (class "Default")
      (node (ref "U1") (pin "31") (pinfunction "SD_D11/__SRAM_D11__/GPIO100_/I2S_LRCK_/NAND_WR#_/UART0_TX_/CAN1_TX_31") (pintype "passive"))
      (node (ref "U3") (pin "47") (pinfunction "I/O11_47") (pintype "passive"))
    )
    (net (code "131") (name "/SDRAM_D12") (class "Default")
      (node (ref "U1") (pin "30") (pinfunction "SD_D12/__SRAM_D13/_GPIO101_/UART1_RX_/NAND_RDY_/I2C_SDA1_/PWM0_30") (pintype "passive"))
      (node (ref "U3") (pin "48") (pinfunction "I/O12_48") (pintype "passive"))
    )
    (net (code "132") (name "/SDRAM_D13") (class "Default")
      (node (ref "U1") (pin "29") (pinfunction "SD_D13/__SRAM_D13__/GPIO102_/UART1_TX_/NAND_CE#_/I2C_SCL1_/PWM1_29") (pintype "passive"))
      (node (ref "U3") (pin "50") (pinfunction "I/O13_50") (pintype "passive"))
    )
    (net (code "133") (name "/SDRAM_D14") (class "Default")
      (node (ref "U1") (pin "28") (pinfunction "SD_D14/__SRAM_D14__/GPIO103_/I2C_SDA/_PWM2_/UART2_RX_/MDC_28") (pintype "passive"))
      (node (ref "U3") (pin "51") (pinfunction "I/O14_51") (pintype "passive"))
    )
    (net (code "134") (name "/SDRAM_D15") (class "Default")
      (node (ref "U1") (pin "27") (pinfunction "SD_D15/__SRAM_D15_/GPIO104_/I2C_SCL_/PWM3_/UART2_TX_/MDIO_27") (pintype "passive"))
      (node (ref "U3") (pin "53") (pinfunction "I/O15_53") (pintype "passive"))
    )
    (net (code "135") (name "/SDRAM_DQM0") (class "Default")
      (node (ref "U1") (pin "36") (pinfunction "SD_DQM0/__SRAM_BLEn_36") (pintype "passive"))
      (node (ref "U3") (pin "15") (pinfunction "LDQM_15") (pintype "passive"))
    )
    (net (code "136") (name "/SDRAM_DQM1") (class "Default")
      (node (ref "U1") (pin "35") (pinfunction "SD_DQM1/__SRAM_BHEn__/GPIO96_/I2S_DO_/PWM1_/XTALI_/UART6_RX/__UART0_DCD_35") (pintype "passive"))
      (node (ref "U3") (pin "39") (pinfunction "UDQM_39") (pintype "passive"))
    )
    (net (code "137") (name "/SPI0_CLK") (class "Default")
      (node (ref "R17") (pin "1") (pinfunction "1_1") (pintype "passive"))
      (node (ref "U1") (pin "94") (pinfunction "SPI_CLK_/GPIO78_/Sdio_clk_/UART5_TX/__UART0_DTR_94") (pintype "passive"))
      (node (ref "U2") (pin "3") (pinfunction "S2A_3") (pintype "passive"))
    )
    (net (code "138") (name "/SPI0_CS0") (class "Default")
      (node (ref "U1") (pin "92") (pinfunction "SPI0_CS0_/GPIO81_/Sdio_Dat1_/SDRAM_CS1_/UART5_RX/__UART0_DSR_92") (pintype "passive"))
      (node (ref "U2") (pin "13") (pinfunction "S2D_13") (pintype "passive"))
    )
    (net (code "139") (name "/SPI0_MISO") (class "Default")
      (node (ref "R19") (pin "1") (pinfunction "1_1") (pintype "passive"))
      (node (ref "U1") (pin "90") (pinfunction "SPI0_MISO_/GPIO80_/Sdio_Cmd_/UART4_RX/__UART0_CTS_90") (pintype "passive"))
      (node (ref "U2") (pin "10") (pinfunction "S2C_10") (pintype "passive"))
    )
    (net (code "140") (name "/SPI0_MOSI") (class "Default")
      (node (ref "R18") (pin "1") (pinfunction "1_1") (pintype "passive"))
      (node (ref "U1") (pin "91") (pinfunction "SPI0_MOSI_/GPIO79_/Sdio_Dat0_/UART4_TX/__UART0_RTS_91") (pintype "passive"))
      (node (ref "U2") (pin "6") (pinfunction "S2B_6") (pintype "passive"))
    )
    (net (code "141") (name "/UART2_RX") (class "Default")
      (node (ref "P2") (pin "15") (pinfunction "15_15") (pintype "passive"))
      (node (ref "U1") (pin "149") (pinfunction "MAC_COL_/GPIO36_/CAMDATA0_/UART2_RX_/LCD_R1_/SPI1_CS0/__Sdio_Dat1_149") (pintype "passive"))
      (node (ref "U6") (pin "5") (pinfunction "ERR#_5") (pintype "passive"))
    )
    (net (code "142") (name "/UART2_TX") (class "Default")
      (node (ref "P2") (pin "16") (pinfunction "16_16") (pintype "passive"))
      (node (ref "U1") (pin "150") (pinfunction "MAC_RXC_/GPIO37_/PWM3_/UART2_TX_/LCD_R2_/SPI1_CS1/__Sdio_Dat2_150") (pintype "passive"))
      (node (ref "U6") (pin "6") (pinfunction "PEMP_6") (pintype "passive"))
    )
    (net (code "143") (name "/W_CLK") (class "Default")
      (node (ref "U2") (pin "4") (pinfunction "DA_4") (pintype "passive"))
      (node (ref "U4") (pin "6") (pinfunction "CLK_6") (pintype "passive"))
    )
    (net (code "144") (name "/W_MISO") (class "Default")
      (node (ref "U2") (pin "9") (pinfunction "DC_9") (pintype "passive"))
      (node (ref "U4") (pin "2") (pinfunction "MISO_2") (pintype "passive"))
    )
    (net (code "145") (name "/W_MOSI") (class "Default")
      (node (ref "U2") (pin "7") (pinfunction "DB_7") (pintype "passive"))
      (node (ref "U4") (pin "5") (pinfunction "MOSI_5") (pintype "passive"))
    )
    (net (code "146") (name "/XTALI") (class "Default")
      (node (ref "C1") (pin "2") (pinfunction "2_2") (pintype "passive"))
      (node (ref "R40") (pin "2") (pinfunction "2_2") (pintype "passive"))
      (node (ref "U1") (pin "1") (pinfunction "XTALI_1") (pintype "passive"))
      (node (ref "Y1") (pin "1") (pinfunction "OSC1_1") (pintype "passive"))
    )
    (net (code "147") (name "/XTALO") (class "Default")
      (node (ref "C2") (pin "2") (pinfunction "2_2") (pintype "passive"))
      (node (ref "R40") (pin "1") (pinfunction "1_1") (pintype "passive"))
      (node (ref "U1") (pin "2") (pinfunction "XTAL0_2") (pintype "passive"))
      (node (ref "Y1") (pin "2") (pinfunction "OSC2_2") (pintype "passive"))
    )
    (net (code "148") (name "/~{CH_CS}") (class "Default")
      (node (ref "U2") (pin "14") (pinfunction "S1D_14") (pintype "passive"))
      (node (ref "U6") (pin "15") (pinfunction "D0_15") (pintype "bidirectional"))
    )
    (net (code "149") (name "/~{SDRAM_CAS}") (class "Default")
      (node (ref "R23") (pin "2") (pinfunction "2_2") (pintype "passive"))
      (node (ref "U1") (pin "47") (pinfunction "SD_CASn/__SRAM_A15_47") (pintype "passive"))
      (node (ref "U3") (pin "17") (pinfunction "~{CAS}_17") (pintype "passive"))
    )
    (net (code "150") (name "/~{SDRAM_CS}") (class "Default")
      (node (ref "R21") (pin "2") (pinfunction "2_2") (pintype "passive"))
      (node (ref "U1") (pin "49") (pinfunction "SD_CSn/__SRAM_CSn_49") (pintype "passive"))
      (node (ref "U3") (pin "19") (pinfunction "~{CS}_19") (pintype "passive"))
    )
    (net (code "151") (name "/~{SDRAM_RAS}") (class "Default")
      (node (ref "R22") (pin "2") (pinfunction "2_2") (pintype "passive"))
      (node (ref "U1") (pin "48") (pinfunction "SD_RASn/__SRAM_A14_48") (pintype "passive"))
      (node (ref "U3") (pin "18") (pinfunction "~{RAS}_18") (pintype "passive"))
    )
    (net (code "152") (name "/~{SDRAM_WE}") (class "Default")
      (node (ref "R24") (pin "2") (pinfunction "2_2") (pintype "passive"))
      (node (ref "U1") (pin "46") (pinfunction "SD_WEn/__SRAM_WEn_46") (pintype "passive"))
      (node (ref "U3") (pin "16") (pinfunction "~{WE}_16") (pintype "passive"))
    )
    (net (code "153") (name "/~{SPI_HOLD}") (class "Default")
      (node (ref "R5") (pin "2") (pinfunction "2_2") (pintype "passive"))
      (node (ref "U4") (pin "7") (pinfunction "~{HOLD}_7") (pintype "passive"))
    )
    (net (code "154") (name "/~{SPI_WP}") (class "Default")
      (node (ref "R7") (pin "2") (pinfunction "2_2") (pintype "passive"))
      (node (ref "U4") (pin "3") (pinfunction "~{WP}_3") (pintype "passive"))
    )
    (net (code "155") (name "/~{SYS_RESET}") (class "Default")
      (node (ref "C32") (pin "2") (pinfunction "2_2") (pintype "passive"))
      (node (ref "P3") (pin "11") (pinfunction "11_11") (pintype "passive"))
      (node (ref "R9") (pin "1") (pinfunction "1_1") (pintype "passive"))
      (node (ref "S2") (pin "2") (pinfunction "2_2") (pintype "passive"))
      (node (ref "U1") (pin "125") (pinfunction "~{SYS_RST}_125") (pintype "passive"))
    )
    (net (code "156") (name "1V2") (class "Default")
      (node (ref "C20") (pin "2") (pinfunction "2_2") (pintype "passive"))
      (node (ref "C21") (pin "2") (pinfunction "2_2") (pintype "passive"))
      (node (ref "C22") (pin "2") (pinfunction "2_2") (pintype "passive"))
      (node (ref "C23") (pin "2") (pinfunction "2_2") (pintype "passive"))
      (node (ref "C24") (pin "2") (pinfunction "2_2") (pintype "passive"))
      (node (ref "C25") (pin "2") (pinfunction "2_2") (pintype "passive"))
      (node (ref "C26") (pin "2") (pinfunction "2_2") (pintype "passive"))
      (node (ref "C27") (pin "2") (pinfunction "2_2") (pintype "passive"))
      (node (ref "C28") (pin "2") (pinfunction "2_2") (pintype "passive"))
      (node (ref "C29") (pin "2") (pinfunction "2_2") (pintype "passive"))
      (node (ref "C30") (pin "2") (pinfunction "2_2") (pintype "passive"))
      (node (ref "C31") (pin "2") (pinfunction "2_2") (pintype "passive"))
      (node (ref "C60") (pin "1") (pinfunction "1_1") (pintype "passive"))
      (node (ref "C61") (pin "1") (pinfunction "1_1") (pintype "passive"))
      (node (ref "C62") (pin "2") (pinfunction "2_2") (pintype "passive"))
      (node (ref "L2") (pin "1") (pinfunction "1_1") (pintype "passive"))
      (node (ref "R13") (pin "2") (pinfunction "2_2") (pintype "passive"))
      (node (ref "U1") (pin "101") (pinfunction "CORE_VDD_101") (pintype "passive"))
      (node (ref "U1") (pin "11") (pinfunction "CORE_VDD_11") (pintype "passive"))
      (node (ref "U1") (pin "124") (pinfunction "CORE_VDD_124") (pintype "passive"))
      (node (ref "U1") (pin "152") (pinfunction "CORE_VDD_152") (pintype "passive"))
      (node (ref "U1") (pin "154") (pinfunction "OTG_DVDD_154") (pintype "passive"))
      (node (ref "U1") (pin "164") (pinfunction "USB_DVDD_164") (pintype "passive"))
      (node (ref "U1") (pin "171") (pinfunction "PLL_VDD12_171") (pintype "passive"))
      (node (ref "U1") (pin "26") (pinfunction "CORE_VDD_26") (pintype "passive"))
      (node (ref "U1") (pin "68") (pinfunction "CORE_VDD_68") (pintype "passive"))
    )
    (net (code "157") (name "3V3") (class "Default")
      (node (ref "C10") (pin "2") (pinfunction "2_2") (pintype "passive"))
      (node (ref "C11") (pin "2") (pinfunction "2_2") (pintype "passive"))
      (node (ref "C12") (pin "2") (pinfunction "2_2") (pintype "passive"))
      (node (ref "C13") (pin "2") (pinfunction "2_2") (pintype "passive"))
      (node (ref "C14") (pin "2") (pinfunction "2_2") (pintype "passive"))
      (node (ref "C15") (pin "2") (pinfunction "2_2") (pintype "passive"))
      (node (ref "C16") (pin "2") (pinfunction "2_2") (pintype "passive"))
      (node (ref "C17") (pin "2") (pinfunction "2_2") (pintype "passive"))
      (node (ref "C37") (pin "2") (pinfunction "2_2") (pintype "passive"))
      (node (ref "C38") (pin "2") (pinfunction "2_2") (pintype "passive"))
      (node (ref "C39") (pin "2") (pinfunction "2_2") (pintype "passive"))
      (node (ref "C40") (pin "2") (pinfunction "2_2") (pintype "passive"))
      (node (ref "C41") (pin "2") (pinfunction "2_2") (pintype "passive"))
      (node (ref "C42") (pin "2") (pinfunction "2_2") (pintype "passive"))
      (node (ref "C43") (pin "2") (pinfunction "2_2") (pintype "passive"))
      (node (ref "C44") (pin "2") (pinfunction "2_2") (pintype "passive"))
      (node (ref "C45") (pin "2") (pinfunction "2_2") (pintype "passive"))
      (node (ref "C46") (pin "2") (pinfunction "2_2") (pintype "passive"))
      (node (ref "C47") (pin "2") (pinfunction "2_2") (pintype "passive"))
      (node (ref "C48") (pin "2") (pinfunction "2_2") (pintype "passive"))
      (node (ref "C5") (pin "2") (pinfunction "2_2") (pintype "passive"))
      (node (ref "C52") (pin "2") (pinfunction "2_2") (pintype "passive"))
      (node (ref "C56") (pin "2") (pinfunction "2_2") (pintype "passive"))
      (node (ref "C57") (pin "2") (pinfunction "2_2") (pintype "passive"))
      (node (ref "C58") (pin "2") (pinfunction "2_2") (pintype "passive"))
      (node (ref "C59") (pin "2") (pinfunction "2_2") (pintype "passive"))
      (node (ref "C6") (pin "2") (pinfunction "2_2") (pintype "passive"))
      (node (ref "C67") (pin "1") (pinfunction "1_1") (pintype "passive"))
      (node (ref "C68") (pin "1") (pinfunction "1_1") (pintype "passive"))
      (node (ref "C69") (pin "2") (pinfunction "2_2") (pintype "passive"))
      (node (ref "C7") (pin "2") (pinfunction "2_2") (pintype "passive"))
      (node (ref "C70") (pin "2") (pinfunction "2_2") (pintype "passive"))
      (node (ref "C71") (pin "2") (pinfunction "2_2") (pintype "passive"))
      (node (ref "C8") (pin "2") (pinfunction "2_2") (pintype "passive"))
      (node (ref "C9") (pin "2") (pinfunction "2_2") (pintype "passive"))
      (node (ref "D1") (pin "1") (pinfunction "A_1") (pintype "passive"))
      (node (ref "L1") (pin "1") (pinfunction "1_1") (pintype "passive"))
      (node (ref "L3") (pin "1") (pinfunction "1_1") (pintype "passive"))
      (node (ref "P1") (pin "27") (pinfunction "27_27") (pintype "passive"))
      (node (ref "P1") (pin "28") (pinfunction "28_28") (pintype "passive"))
      (node (ref "P5") (pin "8") (pinfunction "3V3_8") (pintype "passive"))
      (node (ref "R1") (pin "2") (pinfunction "2_2") (pintype "passive"))
      (node (ref "R15") (pin "1") (pinfunction "1_1") (pintype "passive"))
      (node (ref "R17") (pin "2") (pinfunction "2_2") (pintype "passive"))
      (node (ref "R18") (pin "2") (pinfunction "2_2") (pintype "passive"))
      (node (ref "R19") (pin "2") (pinfunction "2_2") (pintype "passive"))
      (node (ref "R21") (pin "1") (pinfunction "1_1") (pintype "passive"))
      (node (ref "R22") (pin "1") (pinfunction "1_1") (pintype "passive"))
      (node (ref "R23") (pin "1") (pinfunction "1_1") (pintype "passive"))
      (node (ref "R24") (pin "1") (pinfunction "1_1") (pintype "passive"))
      (node (ref "R28") (pin "2") (pinfunction "2_2") (pintype "passive"))
      (node (ref "R3") (pin "2") (pinfunction "2_2") (pintype "passive"))
      (node (ref "R30") (pin "2") (pinfunction "2_2") (pintype "passive"))
      (node (ref "R31") (pin "2") (pinfunction "2_2") (pintype "passive"))
      (node (ref "R32") (pin "2") (pinfunction "2_2") (pintype "passive"))
      (node (ref "R33") (pin "2") (pinfunction "2_2") (pintype "passive"))
      (node (ref "R36") (pin "2") (pinfunction "2_2") (pintype "passive"))
      (node (ref "R38") (pin "2") (pinfunction "2_2") (pintype "passive"))
      (node (ref "R42") (pin "2") (pinfunction "2_2") (pintype "passive"))
      (node (ref "R5") (pin "1") (pinfunction "1_1") (pintype "passive"))
      (node (ref "R6") (pin "1") (pinfunction "1_1") (pintype "passive"))
      (node (ref "R7") (pin "1") (pinfunction "1_1") (pintype "passive"))
      (node (ref "R9") (pin "2") (pinfunction "2_2") (pintype "passive"))
      (node (ref "U1") (pin "102") (pinfunction "IO_VDD_102") (pintype "passive"))
      (node (ref "U1") (pin "131") (pinfunction "IO_VDD_131") (pintype "passive"))
      (node (ref "U1") (pin "155") (pinfunction "OTG_VDD33_155") (pintype "passive"))
      (node (ref "U1") (pin "165") (pinfunction "USB_VDD33_165") (pintype "passive"))
      (node (ref "U1") (pin "173") (pinfunction "PLL_VDD33_173") (pintype "passive"))
      (node (ref "U1") (pin "18") (pinfunction "IO_VDD_18") (pintype "passive"))
      (node (ref "U1") (pin "45") (pinfunction "IO_VDD_45") (pintype "passive"))
      (node (ref "U1") (pin "69") (pinfunction "IO_VDD_69") (pintype "passive"))
      (node (ref "U2") (pin "16") (pinfunction "VCC_16") (pintype "passive"))
      (node (ref "U3") (pin "1") (pinfunction "VCC_1") (pintype "passive"))
      (node (ref "U3") (pin "14") (pinfunction "VCC_14") (pintype "passive"))
      (node (ref "U3") (pin "27") (pinfunction "VCC_27") (pintype "passive"))
      (node (ref "U3") (pin "3") (pinfunction "VCCQ_3") (pintype "passive"))
      (node (ref "U3") (pin "43") (pinfunction "VCCQ_43") (pintype "passive"))
      (node (ref "U3") (pin "49") (pinfunction "VCCQ_49") (pintype "passive"))
      (node (ref "U3") (pin "9") (pinfunction "VCCQ_9") (pintype "passive"))
      (node (ref "U4") (pin "8") (pinfunction "VCC_8") (pintype "passive"))
      (node (ref "U6") (pin "28") (pinfunction "VCC_28") (pintype "power_in"))
      (node (ref "U6") (pin "9") (pinfunction "V3_9") (pintype "power_in"))
    )
    (net (code "158") (name "5V") (class "Default")
      (node (ref "C36") (pin "1") (pinfunction "1_1") (pintype "passive"))
      (node (ref "C53") (pin "1") (pinfunction "1_1") (pintype "passive"))
      (node (ref "C54") (pin "2") (pinfunction "2_2") (pintype "passive"))
      (node (ref "C65") (pin "2") (pinfunction "2_2") (pintype "passive"))
      (node (ref "F1") (pin "1") (pinfunction "1_1") (pintype "passive"))
      (node (ref "R10") (pin "1") (pinfunction "1_1") (pintype "passive"))
      (node (ref "R25") (pin "1") (pinfunction "1_1") (pintype "passive"))
      (node (ref "U5") (pin "2") (pinfunction "IN_2") (pintype "passive"))
      (node (ref "U8") (pin "2") (pinfunction "IN_2") (pintype "passive"))
    )
    (net (code "159") (name "5V1") (class "Default")
      (node (ref "P1") (pin "1") (pinfunction "1_1") (pintype "passive"))
      (node (ref "P2") (pin "1") (pinfunction "1_1") (pintype "passive"))
      (node (ref "P8") (pin "A4") (pinfunction "VBUS_A4") (pintype "passive"))
      (node (ref "P8") (pin "A9") (pinfunction "VBUS_A9") (pintype "passive"))
      (node (ref "P8") (pin "B4") (pinfunction "VBUS_B4") (pintype "passive"))
      (node (ref "P8") (pin "B9") (pinfunction "VBUS_B9") (pintype "passive"))
      (node (ref "S1") (pin "2") (pinfunction "NO_2") (pintype "passive"))
    )
    (net (code "160") (name "ADC_VDDA") (class "Default")
      (node (ref "C18") (pin "2") (pinfunction "2_2") (pintype "passive"))
      (node (ref "C19") (pin "2") (pinfunction "2_2") (pintype "passive"))
      (node (ref "L1") (pin "2") (pinfunction "2_2") (pintype "passive"))
      (node (ref "U1") (pin "83") (pinfunction "ADC_VDDA_83") (pintype "passive"))
    )
    (net (code "161") (name "GND") (class "Default")
      (node (ref "C1") (pin "1") (pinfunction "1_1") (pintype "passive"))
      (node (ref "C10") (pin "1") (pinfunction "1_1") (pintype "passive"))
      (node (ref "C11") (pin "1") (pinfunction "1_1") (pintype "passive"))
      (node (ref "C12") (pin "1") (pinfunction "1_1") (pintype "passive"))
      (node (ref "C13") (pin "1") (pinfunction "1_1") (pintype "passive"))
      (node (ref "C14") (pin "1") (pinfunction "1_1") (pintype "passive"))
      (node (ref "C15") (pin "1") (pinfunction "1_1") (pintype "passive"))
      (node (ref "C16") (pin "1") (pinfunction "1_1") (pintype "passive"))
      (node (ref "C17") (pin "1") (pinfunction "1_1") (pintype "passive"))
      (node (ref "C18") (pin "1") (pinfunction "1_1") (pintype "passive"))
      (node (ref "C19") (pin "1") (pinfunction "1_1") (pintype "passive"))
      (node (ref "C2") (pin "1") (pinfunction "1_1") (pintype "passive"))
      (node (ref "C20") (pin "1") (pinfunction "1_1") (pintype "passive"))
      (node (ref "C21") (pin "1") (pinfunction "1_1") (pintype "passive"))
      (node (ref "C22") (pin "1") (pinfunction "1_1") (pintype "passive"))
      (node (ref "C23") (pin "1") (pinfunction "1_1") (pintype "passive"))
      (node (ref "C24") (pin "1") (pinfunction "1_1") (pintype "passive"))
      (node (ref "C25") (pin "1") (pinfunction "1_1") (pintype "passive"))
      (node (ref "C26") (pin "1") (pinfunction "1_1") (pintype "passive"))
      (node (ref "C27") (pin "1") (pinfunction "1_1") (pintype "passive"))
      (node (ref "C28") (pin "1") (pinfunction "1_1") (pintype "passive"))
      (node (ref "C29") (pin "1") (pinfunction "1_1") (pintype "passive"))
      (node (ref "C3") (pin "1") (pinfunction "1_1") (pintype "passive"))
      (node (ref "C30") (pin "1") (pinfunction "1_1") (pintype "passive"))
      (node (ref "C31") (pin "1") (pinfunction "1_1") (pintype "passive"))
      (node (ref "C32") (pin "1") (pinfunction "1_1") (pintype "passive"))
      (node (ref "C33") (pin "2") (pinfunction "2_2") (pintype "passive"))
      (node (ref "C36") (pin "2") (pinfunction "2_2") (pintype "passive"))
      (node (ref "C37") (pin "1") (pinfunction "1_1") (pintype "passive"))
      (node (ref "C38") (pin "1") (pinfunction "1_1") (pintype "passive"))
      (node (ref "C39") (pin "1") (pinfunction "1_1") (pintype "passive"))
      (node (ref "C4") (pin "1") (pinfunction "1_1") (pintype "passive"))
      (node (ref "C40") (pin "1") (pinfunction "1_1") (pintype "passive"))
      (node (ref "C41") (pin "1") (pinfunction "1_1") (pintype "passive"))
      (node (ref "C42") (pin "1") (pinfunction "1_1") (pintype "passive"))
      (node (ref "C43") (pin "1") (pinfunction "1_1") (pintype "passive"))
      (node (ref "C44") (pin "1") (pinfunction "1_1") (pintype "passive"))
      (node (ref "C45") (pin "1") (pinfunction "1_1") (pintype "passive"))
      (node (ref "C46") (pin "1") (pinfunction "1_1") (pintype "passive"))
      (node (ref "C47") (pin "1") (pinfunction "1_1") (pintype "passive"))
      (node (ref "C48") (pin "1") (pinfunction "1_1") (pintype "passive"))
      (node (ref "C49") (pin "2") (pinfunction "2_2") (pintype "passive"))
      (node (ref "C5") (pin "1") (pinfunction "1_1") (pintype "passive"))
      (node (ref "C53") (pin "2") (pinfunction "2_2") (pintype "passive"))
      (node (ref "C54") (pin "1") (pinfunction "1_1") (pintype "passive"))
      (node (ref "C56") (pin "1") (pinfunction "1_1") (pintype "passive"))
      (node (ref "C57") (pin "1") (pinfunction "1_1") (pintype "passive"))
      (node (ref "C58") (pin "1") (pinfunction "1_1") (pintype "passive"))
      (node (ref "C59") (pin "1") (pinfunction "1_1") (pintype "passive"))
      (node (ref "C6") (pin "1") (pinfunction "1_1") (pintype "passive"))
      (node (ref "C60") (pin "2") (pinfunction "2_2") (pintype "passive"))
      (node (ref "C61") (pin "2") (pinfunction "2_2") (pintype "passive"))
      (node (ref "C62") (pin "1") (pinfunction "1_1") (pintype "passive"))
      (node (ref "C63") (pin "1") (pinfunction "1_1") (pintype "passive"))
      (node (ref "C64") (pin "1") (pinfunction "1_1") (pintype "passive"))
      (node (ref "C65") (pin "1") (pinfunction "1_1") (pintype "passive"))
      (node (ref "C67") (pin "2") (pinfunction "2_2") (pintype "passive"))
      (node (ref "C68") (pin "2") (pinfunction "2_2") (pintype "passive"))
      (node (ref "C69") (pin "1") (pinfunction "1_1") (pintype "passive"))
      (node (ref "C7") (pin "1") (pinfunction "1_1") (pintype "passive"))
      (node (ref "C70") (pin "1") (pinfunction "1_1") (pintype "passive"))
      (node (ref "C71") (pin "1") (pinfunction "1_1") (pintype "passive"))
      (node (ref "C8") (pin "1") (pinfunction "1_1") (pintype "passive"))
      (node (ref "C9") (pin "1") (pinfunction "1_1") (pintype "passive"))
      (node (ref "D2") (pin "1") (pinfunction "A_1") (pintype "passive"))
      (node (ref "D4") (pin "1") (pinfunction "A_1") (pintype "passive"))
      (node (ref "D5") (pin "2") (pinfunction "K_2") (pintype "passive"))
      (node (ref "P1") (pin "11") (pinfunction "11_11") (pintype "passive"))
      (node (ref "P1") (pin "18") (pinfunction "18_18") (pintype "passive"))
      (node (ref "P1") (pin "2") (pinfunction "2_2") (pintype "passive"))
      (node (ref "P1") (pin "25") (pinfunction "25_25") (pintype "passive"))
      (node (ref "P1") (pin "26") (pinfunction "26_26") (pintype "passive"))
      (node (ref "P2") (pin "12") (pinfunction "12_12") (pintype "passive"))
      (node (ref "P2") (pin "14") (pinfunction "14_14") (pintype "passive"))
      (node (ref "P2") (pin "2") (pinfunction "2_2") (pintype "passive"))
      (node (ref "P2") (pin "24") (pinfunction "24_24") (pintype "passive"))
      (node (ref "P2") (pin "5") (pinfunction "5_5") (pintype "passive"))
      (node (ref "P2") (pin "9") (pinfunction "9_9") (pintype "passive"))
      (node (ref "P3") (pin "12") (pinfunction "12_12") (pintype "passive"))
      (node (ref "P3") (pin "14") (pinfunction "14_14") (pintype "passive"))
      (node (ref "P3") (pin "5") (pinfunction "5_5") (pintype "passive"))
      (node (ref "P4") (pin "1") (pinfunction "1_1") (pintype "passive"))
      (node (ref "P4") (pin "12") (pinfunction "12_12") (pintype "passive"))
      (node (ref "P4") (pin "13") (pinfunction "13_13") (pintype "passive"))
      (node (ref "P4") (pin "21") (pinfunction "21_21") (pintype "passive"))
      (node (ref "P4") (pin "22") (pinfunction "22_22") (pintype "passive"))
      (node (ref "P5") (pin "10") (pinfunction "GND_10") (pintype "passive"))
      (node (ref "P5") (pin "11") (pinfunction "GND_11") (pintype "passive"))
      (node (ref "P5") (pin "12") (pinfunction "GND_12") (pintype "passive"))
      (node (ref "P5") (pin "13") (pinfunction "GND_13") (pintype "passive"))
      (node (ref "P5") (pin "14") (pinfunction "GND_14") (pintype "passive"))
      (node (ref "P6") (pin "11") (pinfunction "11_11") (pintype "passive"))
      (node (ref "P8") (pin "1") (pinfunction "GND_1") (pintype "passive"))
      (node (ref "P8") (pin "2") (pinfunction "GND_2") (pintype "passive"))
      (node (ref "P8") (pin "3") (pinfunction "GND_3") (pintype "passive"))
      (node (ref "P8") (pin "4") (pinfunction "GND_4") (pintype "passive"))
      (node (ref "P8") (pin "A1") (pinfunction "GND_A1") (pintype "passive"))
      (node (ref "P8") (pin "A12") (pinfunction "GND_A12") (pintype "passive"))
      (node (ref "P8") (pin "B1") (pinfunction "GND_B1") (pintype "passive"))
      (node (ref "P8") (pin "B12") (pinfunction "GND_B12") (pintype "passive"))
      (node (ref "R11") (pin "1") (pinfunction "1_1") (pintype "passive"))
      (node (ref "R12") (pin "2") (pinfunction "2_2") (pintype "passive"))
      (node (ref "R14") (pin "1") (pinfunction "1_1") (pintype "passive"))
      (node (ref "R16") (pin "1") (pinfunction "1_1") (pintype "passive"))
      (node (ref "R2") (pin "1") (pinfunction "1_1") (pintype "passive"))
      (node (ref "R20") (pin "1") (pinfunction "1_1") (pintype "passive"))
      (node (ref "R26") (pin "1") (pinfunction "1_1") (pintype "passive"))
      (node (ref "R27") (pin "2") (pinfunction "2_2") (pintype "passive"))
      (node (ref "R29") (pin "1") (pinfunction "1_1") (pintype "passive"))
      (node (ref "R34") (pin "2") (pinfunction "2_2") (pintype "passive"))
      (node (ref "R35") (pin "2") (pinfunction "2_2") (pintype "passive"))
      (node (ref "R37") (pin "2") (pinfunction "2_2") (pintype "passive"))
      (node (ref "R39") (pin "2") (pinfunction "2_2") (pintype "passive"))
      (node (ref "R4") (pin "1") (pinfunction "1_1") (pintype "passive"))
      (node (ref "R8") (pin "2") (pinfunction "2_2") (pintype "passive"))
      (node (ref "S2") (pin "1") (pinfunction "1_1") (pintype "passive"))
      (node (ref "S3") (pin "1") (pinfunction "COMMON_1") (pintype "passive"))
      (node (ref "U1") (pin "111") (pinfunction "CORE_VSS_111") (pintype "passive"))
      (node (ref "U1") (pin "142") (pinfunction "CORE_VSS_142") (pintype "passive"))
      (node (ref "U1") (pin "153") (pinfunction "OTG_DVSS_153") (pintype "passive"))
      (node (ref "U1") (pin "156") (pinfunction "OTG_VSS33_156") (pintype "passive"))
      (node (ref "U1") (pin "162") (pinfunction "CORE_VSS_162") (pintype "passive"))
      (node (ref "U1") (pin "163") (pinfunction "USB_DVSS_163") (pintype "passive"))
      (node (ref "U1") (pin "166") (pinfunction "USB_VSS33_166") (pintype "passive"))
      (node (ref "U1") (pin "170") (pinfunction "PLL_VSS12_170") (pintype "passive"))
      (node (ref "U1") (pin "172") (pinfunction "PLL_VSS33_172") (pintype "passive"))
      (node (ref "U1") (pin "22") (pinfunction "CORE_VSS_22") (pintype "passive"))
      (node (ref "U1") (pin "51") (pinfunction "CORE_VSS_51") (pintype "passive"))
      (node (ref "U1") (pin "80") (pinfunction "CORE_VSS_80") (pintype "passive"))
      (node (ref "U1") (pin "84") (pinfunction "ADC_VSSA_84") (pintype "passive"))
      (node (ref "U2") (pin "15") (pinfunction "~{EN}_15") (pintype "passive"))
      (node (ref "U2") (pin "8") (pinfunction "GND_8") (pintype "passive"))
      (node (ref "U3") (pin "12") (pinfunction "GNDQ_12") (pintype "passive"))
      (node (ref "U3") (pin "28") (pinfunction "GND_28") (pintype "passive"))
      (node (ref "U3") (pin "41") (pinfunction "GND_41") (pintype "passive"))
      (node (ref "U3") (pin "46") (pinfunction "GNDQ_46") (pintype "passive"))
      (node (ref "U3") (pin "52") (pinfunction "GNDQ_52") (pintype "passive"))
      (node (ref "U3") (pin "54") (pinfunction "GND_54") (pintype "passive"))
      (node (ref "U3") (pin "6") (pinfunction "GNDQ_6") (pintype "passive"))
      (node (ref "U4") (pin "4") (pinfunction "GND_4") (pintype "passive"))
      (node (ref "U5") (pin "4") (pinfunction "GND_4") (pintype "passive"))
      (node (ref "U6") (pin "12") (pinfunction "GND_12") (pintype "power_in"))
      (node (ref "U6") (pin "27") (pinfunction "BUSY_27") (pintype "input"))
      (node (ref "U8") (pin "4") (pinfunction "GND_4") (pintype "passive"))
    )
    (net (code "162") (name "Net-(C35-Pad1)") (class "Default")
      (node (ref "C35") (pin "1") (pinfunction "1_1") (pintype "passive"))
      (node (ref "R26") (pin "2") (pinfunction "2_2") (pintype "passive"))
    )
    (net (code "163") (name "Net-(C51-Pad1)") (class "Default")
      (node (ref "C51") (pin "1") (pinfunction "1_1") (pintype "passive"))
      (node (ref "R11") (pin "2") (pinfunction "2_2") (pintype "passive"))
    )
    (net (code "164") (name "Net-(C55-Pad1)") (class "Default")
      (node (ref "C55") (pin "1") (pinfunction "1_1") (pintype "passive"))
      (node (ref "R12") (pin "1") (pinfunction "1_1") (pintype "passive"))
    )
    (net (code "165") (name "Net-(C66-Pad1)") (class "Default")
      (node (ref "C66") (pin "1") (pinfunction "1_1") (pintype "passive"))
      (node (ref "R27") (pin "1") (pinfunction "1_1") (pintype "passive"))
    )
    (net (code "166") (name "Net-(D2-K)") (class "Default")
      (node (ref "C34") (pin "2") (pinfunction "2_2") (pintype "passive"))
      (node (ref "C66") (pin "2") (pinfunction "2_2") (pintype "passive"))
      (node (ref "D2") (pin "2") (pinfunction "K_2") (pintype "passive"))
      (node (ref "L3") (pin "2") (pinfunction "2_2") (pintype "passive"))
      (node (ref "U8") (pin "3") (pinfunction "SW_3") (pintype "passive"))
    )
    (net (code "167") (name "Net-(D3-A)") (class "Default")
      (node (ref "D3") (pin "1") (pinfunction "A_1") (pintype "passive"))
      (node (ref "R3") (pin "1") (pinfunction "1_1") (pintype "passive"))
    )
    (net (code "168") (name "Net-(D4-K)") (class "Default")
      (node (ref "C50") (pin "2") (pinfunction "2_2") (pintype "passive"))
      (node (ref "C55") (pin "2") (pinfunction "2_2") (pintype "passive"))
      (node (ref "D4") (pin "2") (pinfunction "K_2") (pintype "passive"))
      (node (ref "L2") (pin "2") (pinfunction "2_2") (pintype "passive"))
      (node (ref "U5") (pin "3") (pinfunction "SW_3") (pintype "passive"))
    )
    (net (code "169") (name "Net-(D5-A)") (class "Default")
      (node (ref "D5") (pin "1") (pinfunction "A_1") (pintype "passive"))
      (node (ref "R1") (pin "1") (pinfunction "1_1") (pintype "passive"))
    )
    (net (code "170") (name "Net-(S1-COMMON)") (class "Default")
      (node (ref "F1") (pin "2") (pinfunction "2_2") (pintype "passive"))
      (node (ref "S1") (pin "1") (pinfunction "COMMON_1") (pintype "passive"))
    )
    (net (code "171") (name "Net-(U1-ADC_REXT)") (class "Default")
      (node (ref "R20") (pin "2") (pinfunction "2_2") (pintype "passive"))
      (node (ref "U1") (pin "81") (pinfunction "ADC_REXT_81") (pintype "passive"))
    )
    (net (code "172") (name "Net-(U1-OTG_REXT)") (class "Default")
      (node (ref "R4") (pin "2") (pinfunction "2_2") (pintype "passive"))
      (node (ref "U1") (pin "159") (pinfunction "OTG_REXT_159") (pintype "passive"))
    )
    (net (code "173") (name "Net-(U1-USB_REXT)") (class "Default")
      (node (ref "R2") (pin "2") (pinfunction "2_2") (pintype "passive"))
      (node (ref "U1") (pin "167") (pinfunction "USB_REXT_167") (pintype "passive"))
    )
    (net (code "174") (name "Net-(U5-BS)") (class "Default")
      (node (ref "C50") (pin "1") (pinfunction "1_1") (pintype "passive"))
      (node (ref "U5") (pin "1") (pinfunction "BS_1") (pintype "passive"))
    )
    (net (code "175") (name "Net-(U5-COMP)") (class "Default")
      (node (ref "C51") (pin "2") (pinfunction "2_2") (pintype "passive"))
      (node (ref "U5") (pin "6") (pinfunction "COMP_6") (pintype "passive"))
    )
    (net (code "176") (name "Net-(U5-EN)") (class "Default")
      (node (ref "R10") (pin "2") (pinfunction "2_2") (pintype "passive"))
      (node (ref "U5") (pin "7") (pinfunction "EN_7") (pintype "passive"))
    )
    (net (code "177") (name "Net-(U5-FB)") (class "Default")
      (node (ref "R13") (pin "1") (pinfunction "1_1") (pintype "passive"))
      (node (ref "R14") (pin "2") (pinfunction "2_2") (pintype "passive"))
      (node (ref "U5") (pin "5") (pinfunction "FB_5") (pintype "passive"))
    )
    (net (code "178") (name "Net-(U5-SS)") (class "Default")
      (node (ref "C49") (pin "1") (pinfunction "1_1") (pintype "passive"))
      (node (ref "U5") (pin "8") (pinfunction "SS_8") (pintype "passive"))
    )
    (net (code "179") (name "Net-(U6-RSTI)") (class "Default")
      (node (ref "C52") (pin "1") (pinfunction "1_1") (pintype "passive"))
      (node (ref "R8") (pin "1") (pinfunction "1_1") (pintype "passive"))
      (node (ref "U6") (pin "2") (pinfunction "RSTI_2") (pintype "passive"))
    )
    (net (code "180") (name "Net-(U6-XI)") (class "Default")
      (node (ref "C63") (pin "2") (pinfunction "2_2") (pintype "passive"))
      (node (ref "U6") (pin "13") (pinfunction "XI_13") (pintype "passive"))
      (node (ref "Y3") (pin "1") (pinfunction "1_1") (pintype "passive"))
    )
    (net (code "181") (name "Net-(U6-XO)") (class "Default")
      (node (ref "C64") (pin "2") (pinfunction "2_2") (pintype "passive"))
      (node (ref "U6") (pin "14") (pinfunction "XO_14") (pintype "output"))
      (node (ref "Y3") (pin "2") (pinfunction "2_2") (pintype "passive"))
    )
    (net (code "182") (name "Net-(U8-BS)") (class "Default")
      (node (ref "C34") (pin "1") (pinfunction "1_1") (pintype "passive"))
      (node (ref "U8") (pin "1") (pinfunction "BS_1") (pintype "passive"))
    )
    (net (code "183") (name "Net-(U8-COMP)") (class "Default")
      (node (ref "C35") (pin "2") (pinfunction "2_2") (pintype "passive"))
      (node (ref "U8") (pin "6") (pinfunction "COMP_6") (pintype "passive"))
    )
    (net (code "184") (name "Net-(U8-EN)") (class "Default")
      (node (ref "R25") (pin "2") (pinfunction "2_2") (pintype "passive"))
      (node (ref "U8") (pin "7") (pinfunction "EN_7") (pintype "passive"))
    )
    (net (code "185") (name "Net-(U8-FB)") (class "Default")
      (node (ref "R28") (pin "1") (pinfunction "1_1") (pintype "passive"))
      (node (ref "R29") (pin "2") (pinfunction "2_2") (pintype "passive"))
      (node (ref "U8") (pin "5") (pinfunction "FB_5") (pintype "passive"))
    )
    (net (code "186") (name "Net-(U8-SS)") (class "Default")
      (node (ref "C33") (pin "1") (pinfunction "1_1") (pintype "passive"))
      (node (ref "U8") (pin "8") (pinfunction "SS_8") (pintype "passive"))
    )
    (net (code "187") (name "unconnected-(P5-NC-Pad9)") (class "Default")
      (node (ref "P5") (pin "9") (pinfunction "NC_9") (pintype "passive"))
    )
    (net (code "188") (name "unconnected-(P5-RST_N-Pad6)") (class "Default")
      (node (ref "P5") (pin "6") (pinfunction "RST_N_6") (pintype "passive"))
    )
    (net (code "189") (name "unconnected-(P8-CC1-PadA5)") (class "Default")
      (node (ref "P8") (pin "A5") (pinfunction "CC1_A5") (pintype "passive"))
    )
    (net (code "190") (name "unconnected-(P8-CC2-PadB5)") (class "Default")
      (node (ref "P8") (pin "B5") (pinfunction "CC2_B5") (pintype "passive"))
    )
    (net (code "191") (name "unconnected-(P8-NC-PadNC1)") (class "Default")
      (node (ref "P8") (pin "NC1") (pinfunction "NC_NC1") (pintype "passive"))
    )
    (net (code "192") (name "unconnected-(P8-NC-PadNC2)") (class "Default")
      (node (ref "P8") (pin "NC2") (pinfunction "NC_NC2") (pintype "passive"))
    )
    (net (code "193") (name "unconnected-(P8-SBU1-PadA8)") (class "Default")
      (node (ref "P8") (pin "A8") (pinfunction "SBU1_A8") (pintype "passive"))
    )
    (net (code "194") (name "unconnected-(P8-SBU2-PadB8)") (class "Default")
      (node (ref "P8") (pin "B8") (pinfunction "SBU2_B8") (pintype "passive"))
    )
    (net (code "195") (name "unconnected-(P8-SSTXN1-PadA3)") (class "Default")
      (node (ref "P8") (pin "A3") (pinfunction "SSTXN1_A3") (pintype "passive"))
    )
    (net (code "196") (name "unconnected-(P8-SSTXN1-PadB10)") (class "Default")
      (node (ref "P8") (pin "B10") (pinfunction "SSTXN1_B10") (pintype "passive"))
    )
    (net (code "197") (name "unconnected-(P8-SSTXN2-PadA10)") (class "Default")
      (node (ref "P8") (pin "A10") (pinfunction "SSTXN2_A10") (pintype "passive"))
    )
    (net (code "198") (name "unconnected-(P8-SSTXN2-PadB3)") (class "Default")
      (node (ref "P8") (pin "B3") (pinfunction "SSTXN2_B3") (pintype "passive"))
    )
    (net (code "199") (name "unconnected-(P8-SSTXP1-PadA2)") (class "Default")
      (node (ref "P8") (pin "A2") (pinfunction "SSTXP1_A2") (pintype "passive"))
    )
    (net (code "200") (name "unconnected-(P8-SSTXP1-PadB11)") (class "Default")
      (node (ref "P8") (pin "B11") (pinfunction "SSTXP1_B11") (pintype "passive"))
    )
    (net (code "201") (name "unconnected-(P8-SSTXP2-PadA11)") (class "Default")
      (node (ref "P8") (pin "A11") (pinfunction "SSTXP2_A11") (pintype "passive"))
    )
    (net (code "202") (name "unconnected-(P8-SSTXP2-PadB2)") (class "Default")
      (node (ref "P8") (pin "B2") (pinfunction "SSTXP2_B2") (pintype "passive"))
    )
    (net (code "203") (name "unconnected-(U3-NC-Pad40)") (class "Default")
      (node (ref "U3") (pin "40") (pinfunction "NC_40") (pintype "passive"))
    )
    (net (code "204") (name "unconnected-(U6-ACK#-Pad7)") (class "Default")
      (node (ref "U6") (pin "7") (pinfunction "ACK#_7") (pintype "passive"))
    )
    (net (code "205") (name "unconnected-(U6-ACT#-Pad1)") (class "Default")
      (node (ref "U6") (pin "1") (pinfunction "ACT#_1") (pintype "output"))
    )
    (net (code "206") (name "unconnected-(U6-AFD#-Pad4)") (class "Default")
      (node (ref "U6") (pin "4") (pinfunction "AFD#_4") (pintype "output"))
    )
    (net (code "207") (name "unconnected-(U6-D1-Pad16)") (class "Default")
      (node (ref "U6") (pin "16") (pinfunction "D1_16") (pintype "bidirectional"))
    )
    (net (code "208") (name "unconnected-(U6-D2-Pad17)") (class "Default")
      (node (ref "U6") (pin "17") (pinfunction "D2_17") (pintype "bidirectional"))
    )
    (net (code "209") (name "unconnected-(U6-D4-Pad19)") (class "Default")
      (node (ref "U6") (pin "19") (pinfunction "D4_19") (pintype "bidirectional"))
    )
    (net (code "210") (name "unconnected-(U6-D6-Pad21)") (class "Default")
      (node (ref "U6") (pin "21") (pinfunction "D6_21") (pintype "bidirectional"))
    )
    (net (code "211") (name "unconnected-(U6-INI#-Pad26)") (class "Default")
      (node (ref "U6") (pin "26") (pinfunction "INI#_26") (pintype "output"))
    )
    (net (code "212") (name "unconnected-(U6-SCL-Pad24)") (class "Default")
      (node (ref "U6") (pin "24") (pinfunction "SCL_24") (pintype "output"))
    )
    (net (code "213") (name "unconnected-(U6-SIN#-Pad3)") (class "Default")
      (node (ref "U6") (pin "3") (pinfunction "SIN#_3") (pintype "output"))
    )
    (net (code "214") (name "unconnected-(U6-SLCT-Pad8)") (class "Default")
      (node (ref "U6") (pin "8") (pinfunction "SLCT_8") (pintype "passive"))
    )
    (net (code "215") (name "unconnected-(U6-STB#-Pad25)") (class "Default")
      (node (ref "U6") (pin "25") (pinfunction "STB#_25") (pintype "output"))
    )
  )
)
